# LR1302_LoRaWAN_Gateway_Module_V1_0_915US.net
KiCad netlist of a schematic drawn in EAGLE
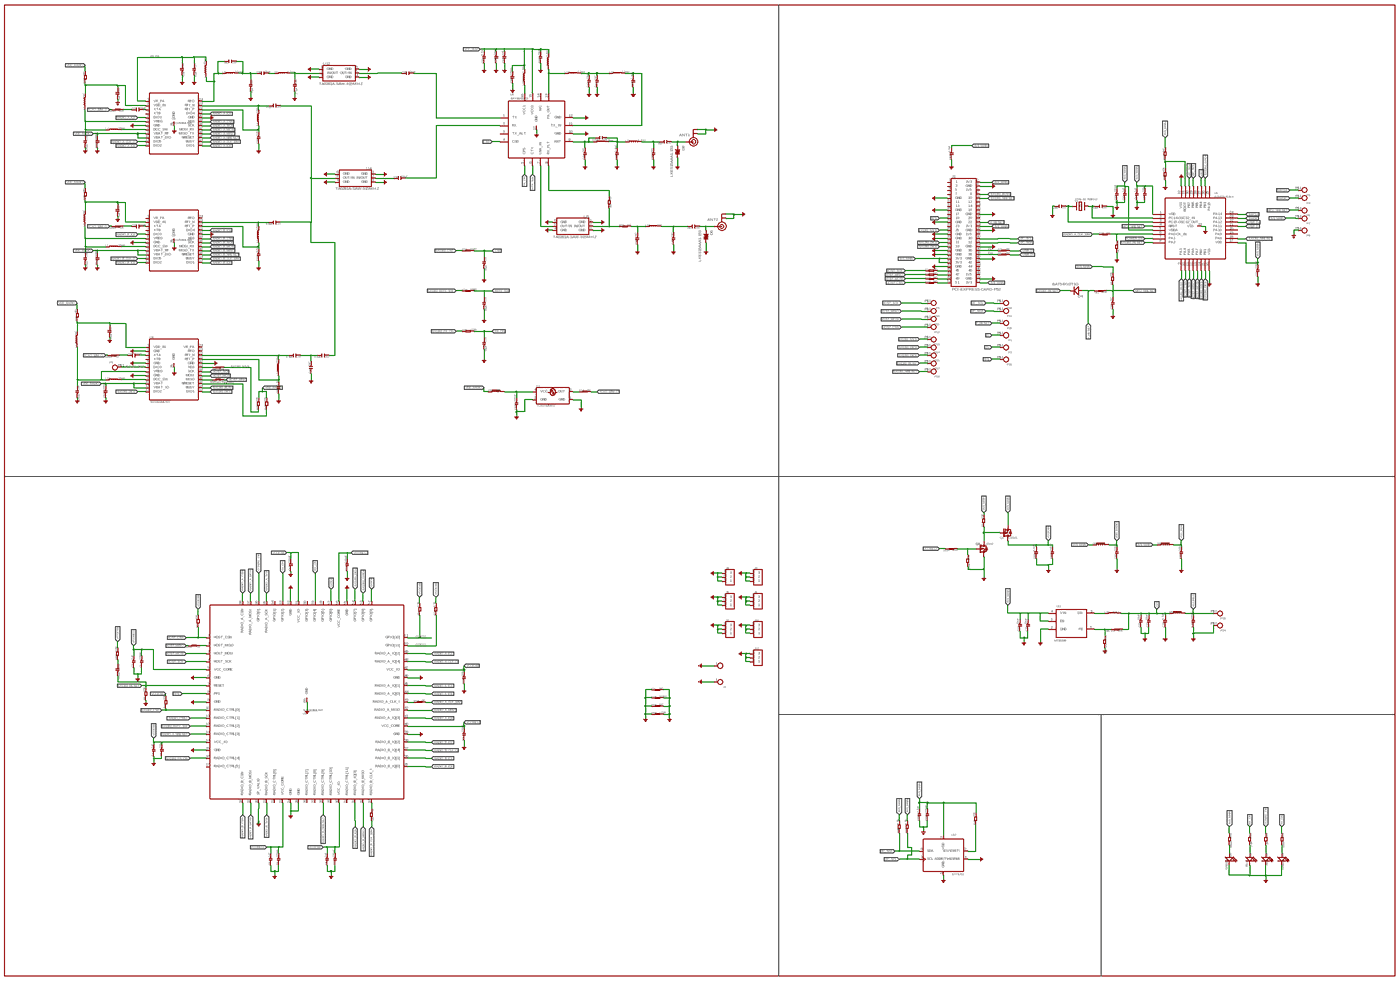
[diagram p0: schematic, sheet 1, overview]
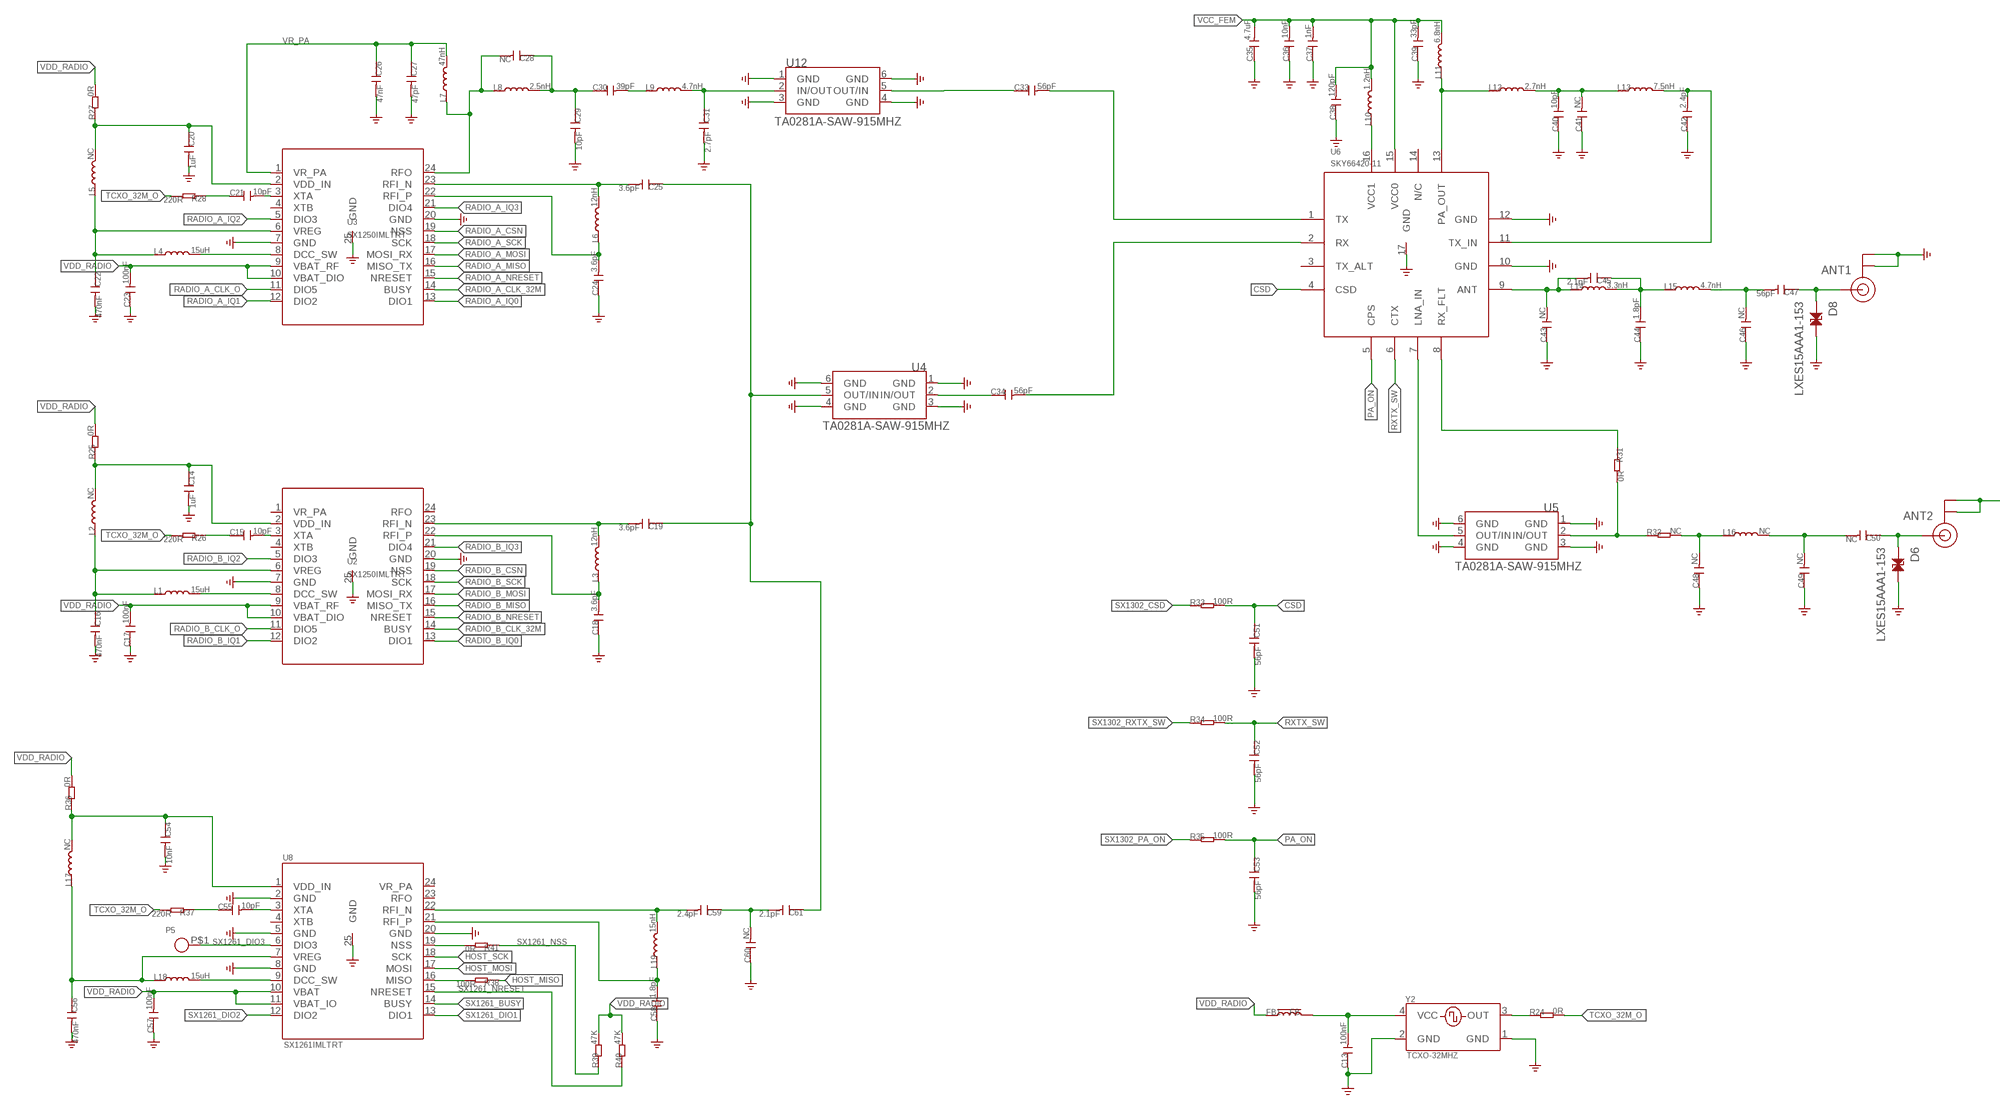
[diagram p1: schematic, sheet 1, part 1 of 4]
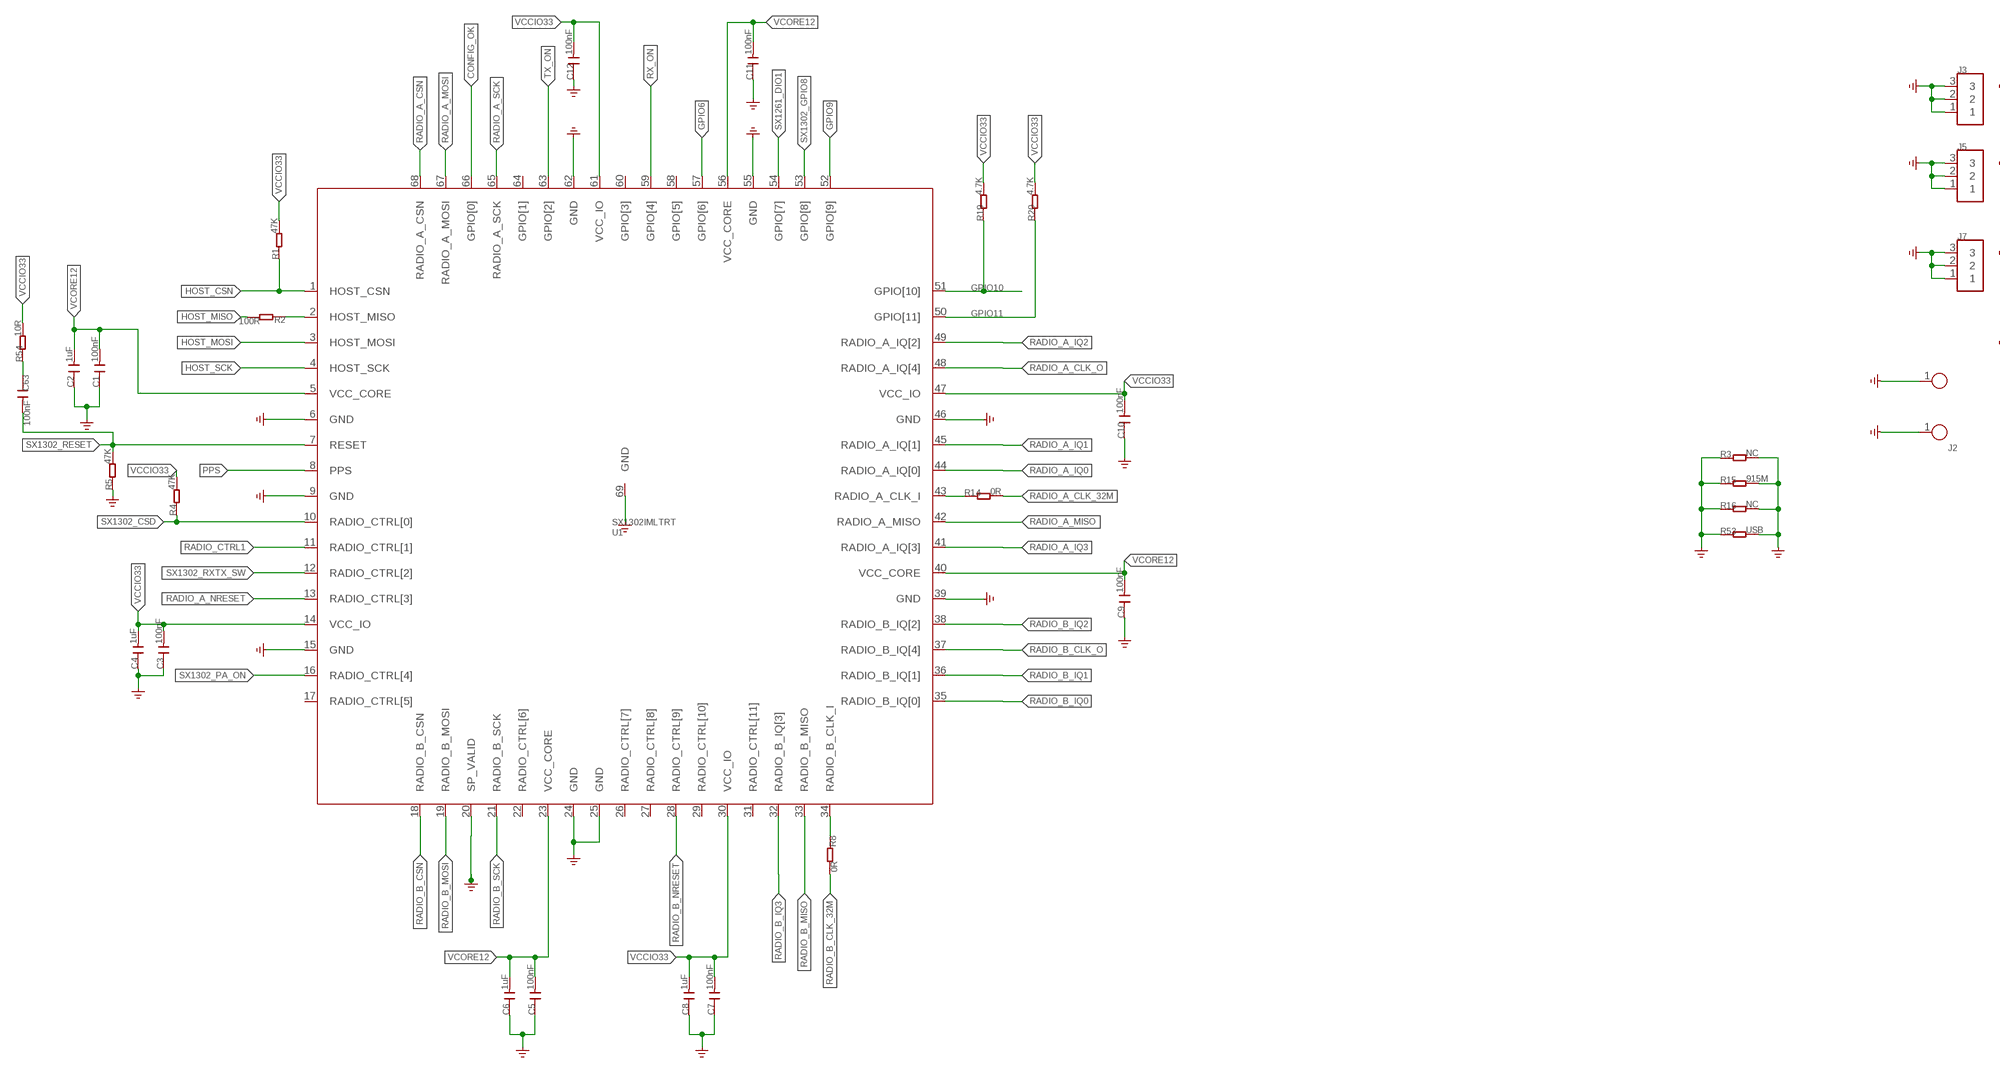
[diagram p2: schematic, sheet 1, part 2 of 4]
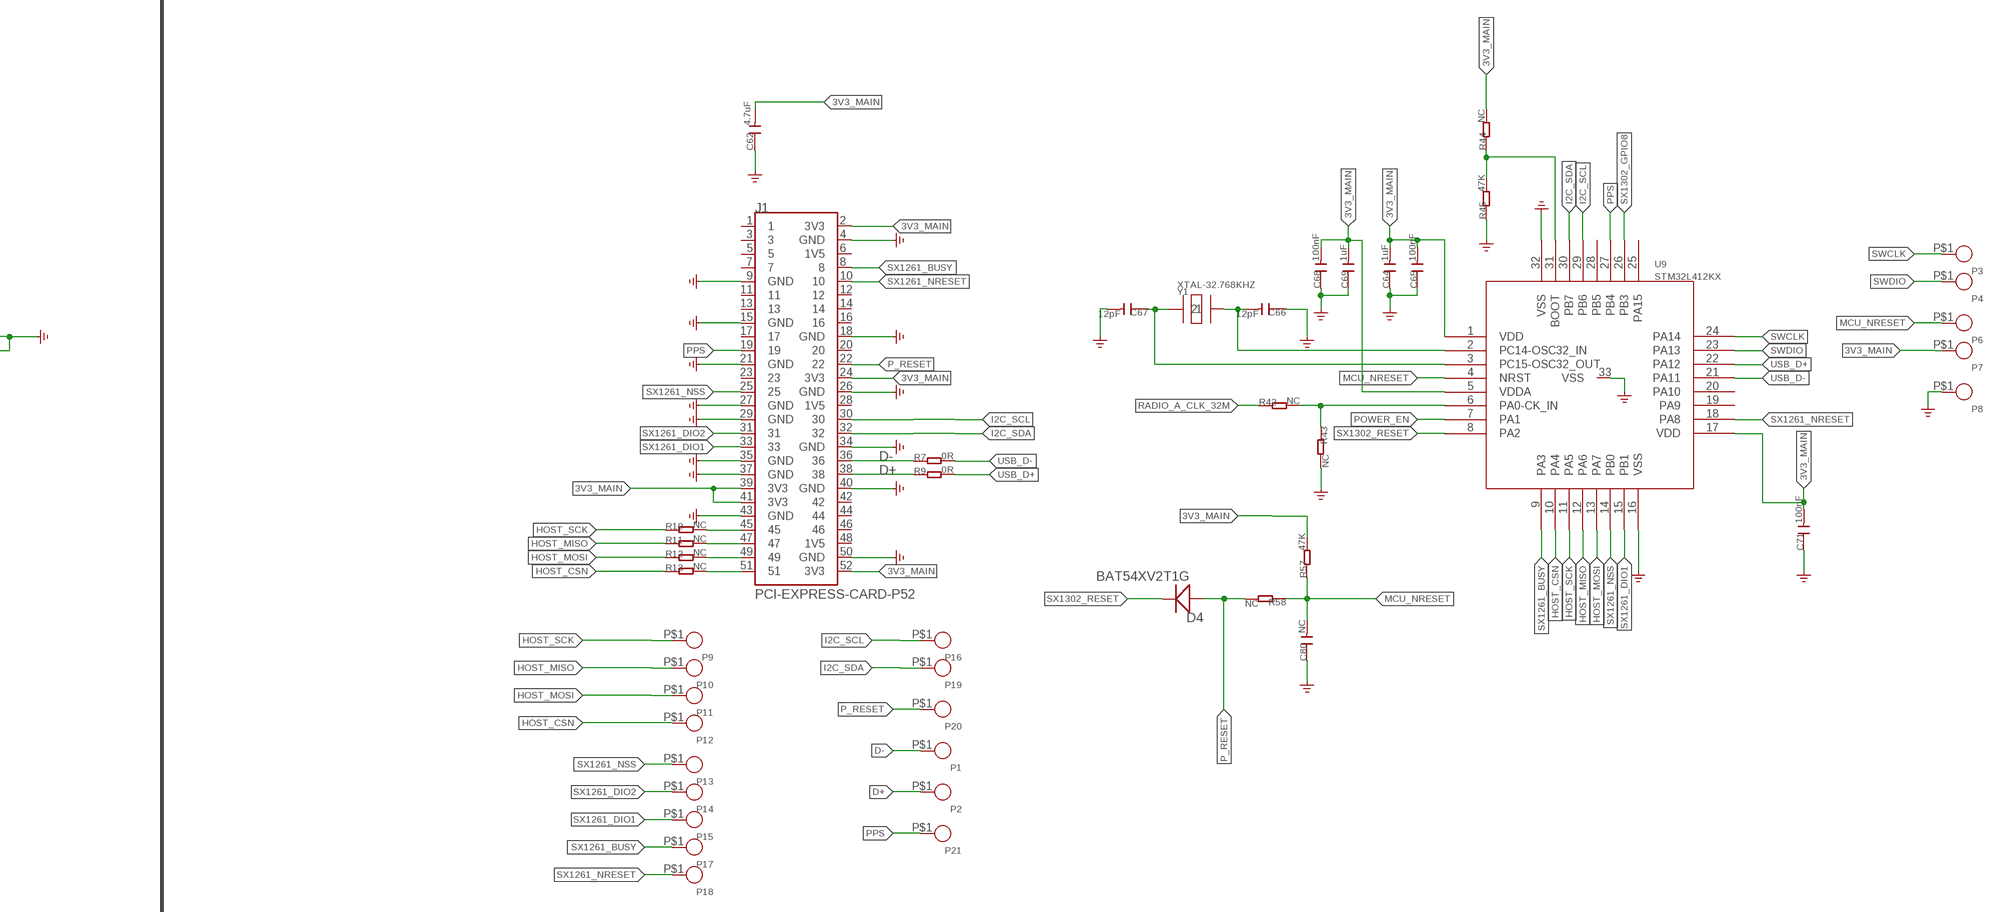
[diagram p3: schematic, sheet 1, part 3 of 4]
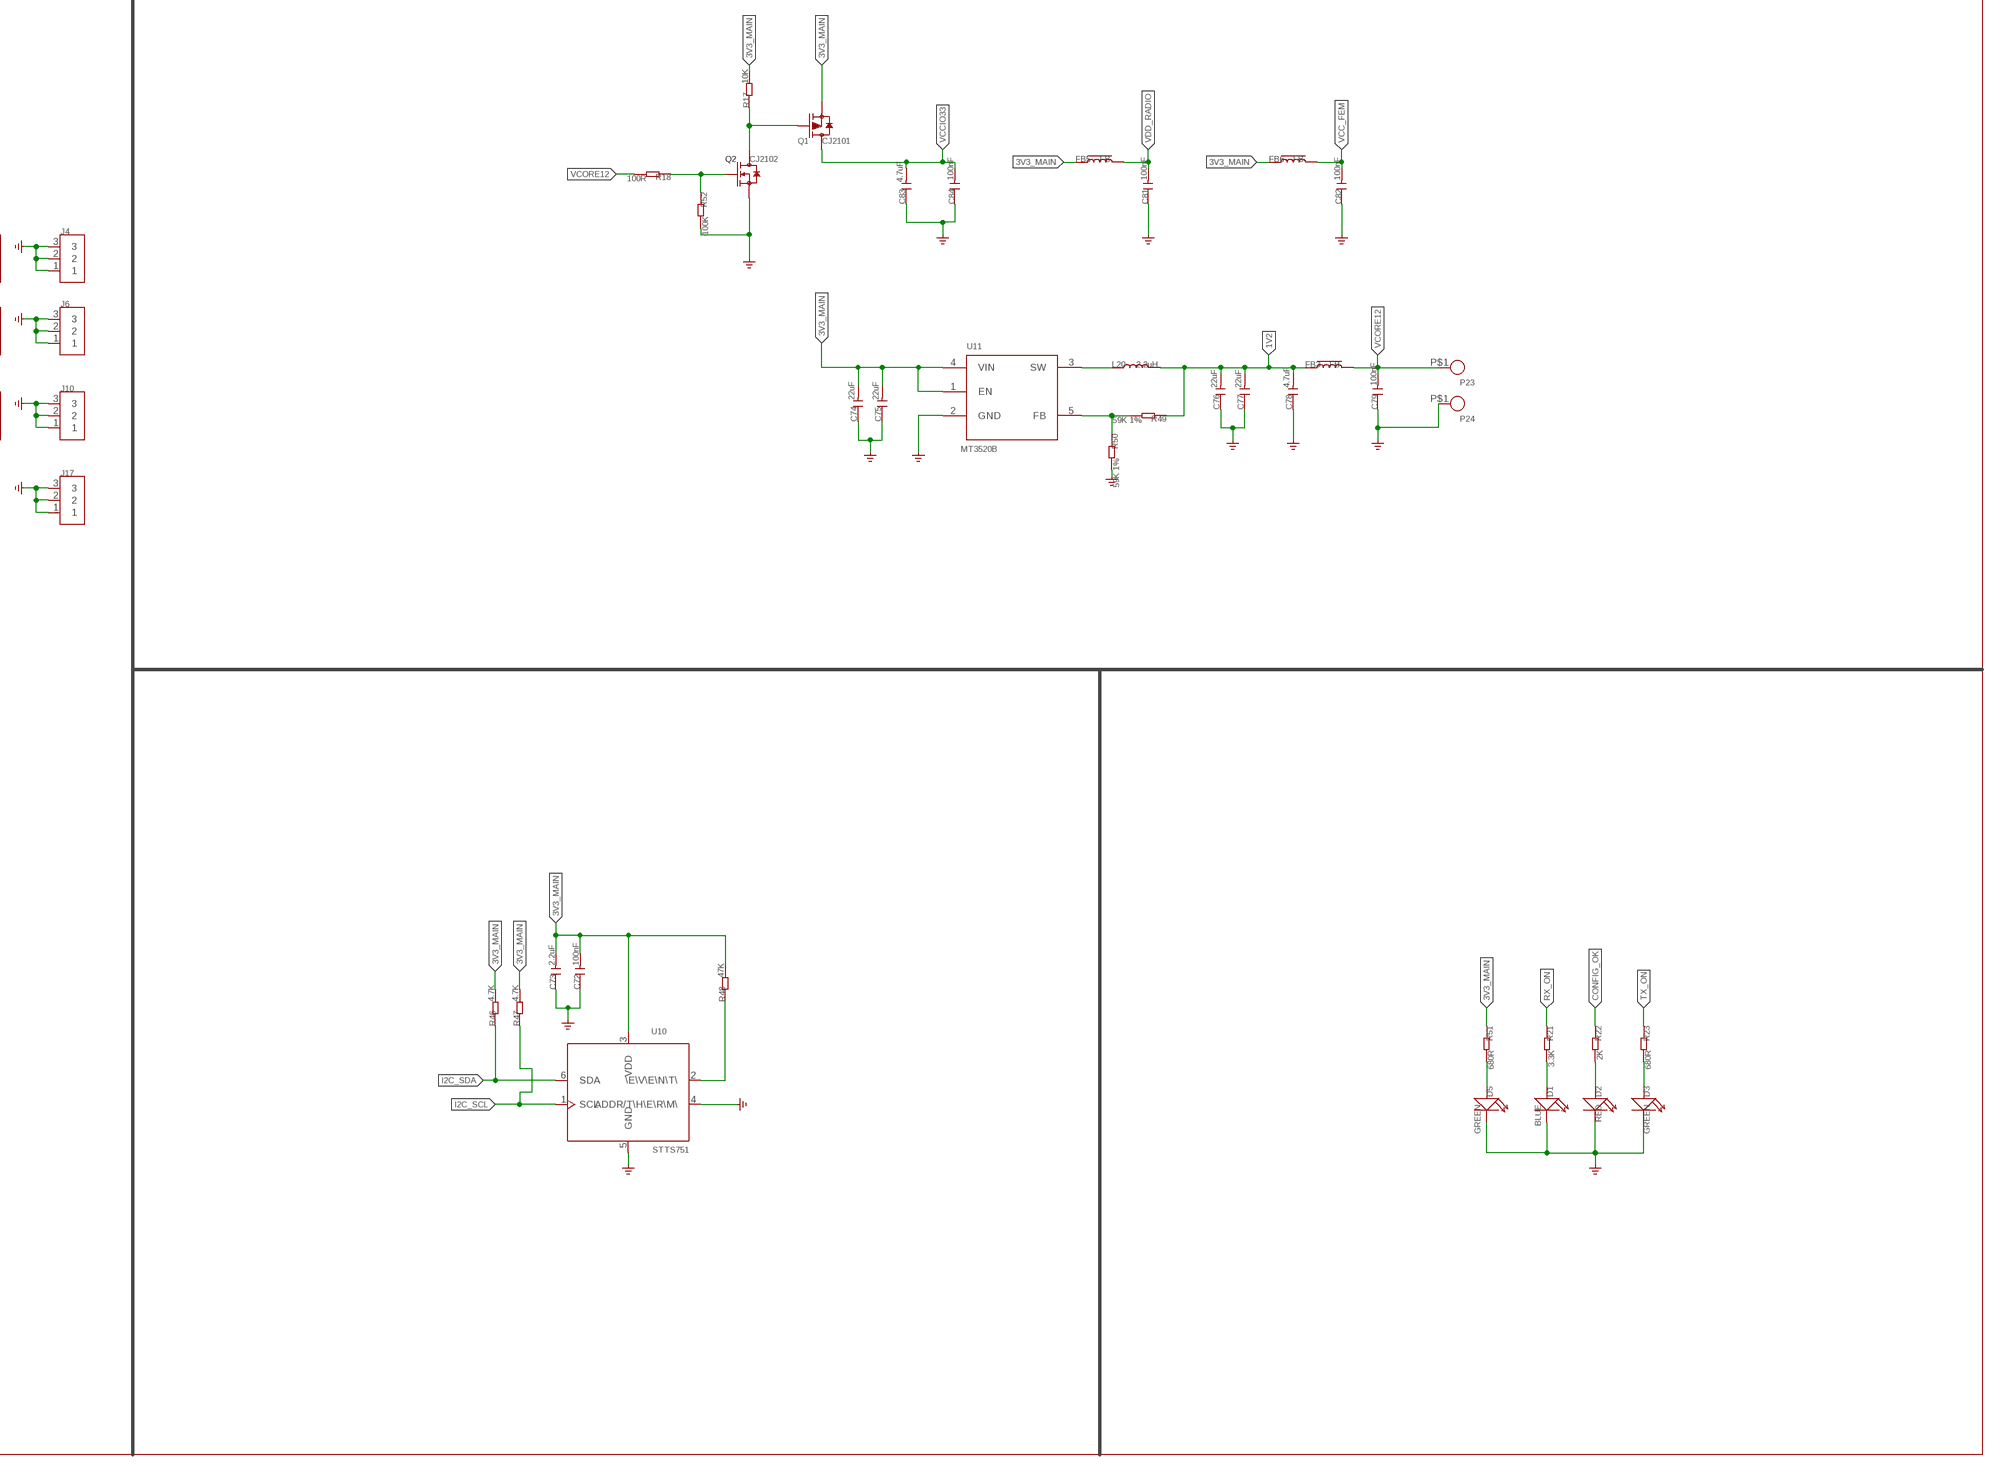
[diagram p4: schematic, sheet 1, part 4 of 4]

(export (version "E")
  (design (tool "Eeschema 10.0.6"))
  (components
    (comp (ref "ANT1")
      (value "U.FL_SMTU.FL-R-SMD")
      (footprint "eagle-import:U.FL-R-SMD")
      (libsource (lib "eagle-import") (part "U.FL_SMTU.FL-R-SMD"))
    )
    (comp (ref "ANT2")
      (value "NC")
      (footprint "eagle-import:U.FL-R-SMD")
      (libsource (lib "eagle-import") (part "U.FL_SMTU.FL-R-SMD"))
    )
    (comp (ref "C1")
      (value "100nF")
      (footprint "eagle-import:C0402")
      (libsource (lib "eagle-import") (part "CAPC0402-1"))
    )
    (comp (ref "C2")
      (value "1uF")
      (footprint "eagle-import:C0402")
      (libsource (lib "eagle-import") (part "CAPC0402-1"))
    )
    (comp (ref "C3")
      (value "100nF")
      (footprint "eagle-import:C0402")
      (libsource (lib "eagle-import") (part "CAPC0402-1"))
    )
    (comp (ref "C4")
      (value "1uF")
      (footprint "eagle-import:C0402")
      (libsource (lib "eagle-import") (part "CAPC0402-1"))
    )
    (comp (ref "C5")
      (value "100nF")
      (footprint "eagle-import:C0402")
      (libsource (lib "eagle-import") (part "CAPC0402-1"))
    )
    (comp (ref "C6")
      (value "1uF")
      (footprint "eagle-import:C0402")
      (libsource (lib "eagle-import") (part "CAPC0402-1"))
    )
    (comp (ref "C7")
      (value "100nF")
      (footprint "eagle-import:C0402")
      (libsource (lib "eagle-import") (part "CAPC0402-1"))
    )
    (comp (ref "C8")
      (value "1uF")
      (footprint "eagle-import:C0402")
      (libsource (lib "eagle-import") (part "CAPC0402-1"))
    )
    (comp (ref "C9")
      (value "100nF")
      (footprint "eagle-import:C0402")
      (libsource (lib "eagle-import") (part "CAPC0402-1"))
    )
    (comp (ref "C10")
      (value "100nF")
      (footprint "eagle-import:C0402")
      (libsource (lib "eagle-import") (part "CAPC0402-1"))
    )
    (comp (ref "C11")
      (value "100nF")
      (footprint "eagle-import:C0402")
      (libsource (lib "eagle-import") (part "CAPC0402-1"))
    )
    (comp (ref "C12")
      (value "100nF")
      (footprint "eagle-import:C0402")
      (libsource (lib "eagle-import") (part "CAPC0402-1"))
    )
    (comp (ref "C13")
      (value "100nF")
      (footprint "eagle-import:C0402")
      (libsource (lib "eagle-import") (part "CAPC0402-1"))
    )
    (comp (ref "C14")
      (value "1uF")
      (footprint "eagle-import:C0402")
      (libsource (lib "eagle-import") (part "CAPC0402-1"))
    )
    (comp (ref "C15")
      (value "10pF")
      (footprint "eagle-import:C0402")
      (libsource (lib "eagle-import") (part "CAPC0402-1"))
    )
    (comp (ref "C16")
      (value "470nF")
      (footprint "eagle-import:C0402")
      (libsource (lib "eagle-import") (part "CAPC0402-1"))
    )
    (comp (ref "C17")
      (value "100nF")
      (footprint "eagle-import:C0402")
      (libsource (lib "eagle-import") (part "CAPC0402-1"))
    )
    (comp (ref "C18")
      (value "3.6pF")
      (footprint "eagle-import:C0402")
      (libsource (lib "eagle-import") (part "CAPC0402-1"))
    )
    (comp (ref "C19")
      (value "3.6pF")
      (footprint "eagle-import:C0402")
      (libsource (lib "eagle-import") (part "CAPC0402-1"))
    )
    (comp (ref "C20")
      (value "1uF")
      (footprint "eagle-import:C0402")
      (libsource (lib "eagle-import") (part "CAPC0402-1"))
    )
    (comp (ref "C21")
      (value "10pF")
      (footprint "eagle-import:C0402")
      (libsource (lib "eagle-import") (part "CAPC0402-1"))
    )
    (comp (ref "C22")
      (value "470nF")
      (footprint "eagle-import:C0402")
      (libsource (lib "eagle-import") (part "CAPC0402-1"))
    )
    (comp (ref "C23")
      (value "100nF")
      (footprint "eagle-import:C0402")
      (libsource (lib "eagle-import") (part "CAPC0402-1"))
    )
    (comp (ref "C24")
      (value "3.6pF")
      (footprint "eagle-import:C0402")
      (libsource (lib "eagle-import") (part "CAPC0402-1"))
    )
    (comp (ref "C25")
      (value "3.6pF")
      (footprint "eagle-import:C0402")
      (libsource (lib "eagle-import") (part "CAPC0402-1"))
    )
    (comp (ref "C26")
      (value "47nF")
      (footprint "eagle-import:C0402")
      (libsource (lib "eagle-import") (part "CAPC0402-1"))
    )
    (comp (ref "C27")
      (value "47pF")
      (footprint "eagle-import:C0402")
      (libsource (lib "eagle-import") (part "CAPC0402-1"))
    )
    (comp (ref "C28")
      (value "NC")
      (footprint "eagle-import:C0402")
      (libsource (lib "eagle-import") (part "CAPC0402-1"))
    )
    (comp (ref "C29")
      (value "10pF")
      (footprint "eagle-import:C0402")
      (libsource (lib "eagle-import") (part "CAPC0402-1"))
    )
    (comp (ref "C30")
      (value "39pF")
      (footprint "eagle-import:C0402")
      (libsource (lib "eagle-import") (part "CAPC0402-1"))
    )
    (comp (ref "C31")
      (value "2.7pF")
      (footprint "eagle-import:C0402")
      (libsource (lib "eagle-import") (part "CAPC0402-1"))
    )
    (comp (ref "C33")
      (value "56pF")
      (footprint "eagle-import:C0402")
      (libsource (lib "eagle-import") (part "CAPC0402-1"))
    )
    (comp (ref "C34")
      (value "56pF")
      (footprint "eagle-import:C0402")
      (libsource (lib "eagle-import") (part "CAPC0402-1"))
    )
    (comp (ref "C35")
      (value "4.7uF")
      (footprint "eagle-import:C0603")
      (libsource (lib "eagle-import") (part "CAP"))
    )
    (comp (ref "C36")
      (value "10nF")
      (footprint "eagle-import:C0402")
      (libsource (lib "eagle-import") (part "CAPC0402-1"))
    )
    (comp (ref "C37")
      (value "1nF")
      (footprint "eagle-import:C0402")
      (libsource (lib "eagle-import") (part "CAPC0402-1"))
    )
    (comp (ref "C38")
      (value "120pF")
      (footprint "eagle-import:C0402")
      (libsource (lib "eagle-import") (part "CAPC0402-1"))
    )
    (comp (ref "C39")
      (value "33pF")
      (footprint "eagle-import:C0402")
      (libsource (lib "eagle-import") (part "CAPC0402-1"))
    )
    (comp (ref "C40")
      (value "10pF")
      (footprint "eagle-import:C0402")
      (libsource (lib "eagle-import") (part "CAPC0402-1"))
    )
    (comp (ref "C41")
      (value "NC")
      (footprint "eagle-import:C0402")
      (libsource (lib "eagle-import") (part "CAPC0402-1"))
    )
    (comp (ref "C42")
      (value "2.4pF")
      (footprint "eagle-import:C0402")
      (libsource (lib "eagle-import") (part "CAPC0402-1"))
    )
    (comp (ref "C43")
      (value "NC")
      (footprint "eagle-import:C0402")
      (libsource (lib "eagle-import") (part "CAPC0402-1"))
    )
    (comp (ref "C44")
      (value "1.8pF")
      (footprint "eagle-import:C0402")
      (libsource (lib "eagle-import") (part "CAPC0402-1"))
    )
    (comp (ref "C45")
      (value "2.1pF")
      (footprint "eagle-import:C0402")
      (libsource (lib "eagle-import") (part "CAPC0402-1"))
    )
    (comp (ref "C46")
      (value "NC")
      (footprint "eagle-import:C0402")
      (libsource (lib "eagle-import") (part "CAPC0402-1"))
    )
    (comp (ref "C47")
      (value "56pF")
      (footprint "eagle-import:C0402")
      (libsource (lib "eagle-import") (part "CAPC0402-1"))
    )
    (comp (ref "C48")
      (value "NC")
      (footprint "eagle-import:C0402")
      (libsource (lib "eagle-import") (part "CAPC0402-1"))
    )
    (comp (ref "C49")
      (value "NC")
      (footprint "eagle-import:C0402")
      (libsource (lib "eagle-import") (part "CAPC0402-1"))
    )
    (comp (ref "C50")
      (value "NC")
      (footprint "eagle-import:C0402")
      (libsource (lib "eagle-import") (part "CAPC0402-1"))
    )
    (comp (ref "C51")
      (value "56pF")
      (footprint "eagle-import:C0402")
      (libsource (lib "eagle-import") (part "CAPC0402-1"))
    )
    (comp (ref "C52")
      (value "56pF")
      (footprint "eagle-import:C0402")
      (libsource (lib "eagle-import") (part "CAPC0402-1"))
    )
    (comp (ref "C53")
      (value "56pF")
      (footprint "eagle-import:C0402")
      (libsource (lib "eagle-import") (part "CAPC0402-1"))
    )
    (comp (ref "C54")
      (value "10nF")
      (footprint "eagle-import:C0402")
      (libsource (lib "eagle-import") (part "CAPC0402-1"))
    )
    (comp (ref "C55")
      (value "10pF")
      (footprint "eagle-import:C0402")
      (libsource (lib "eagle-import") (part "CAPC0402-1"))
    )
    (comp (ref "C56")
      (value "470nF")
      (footprint "eagle-import:C0402")
      (libsource (lib "eagle-import") (part "CAPC0402-1"))
    )
    (comp (ref "C57")
      (value "100nF")
      (footprint "eagle-import:C0402")
      (libsource (lib "eagle-import") (part "CAPC0402-1"))
    )
    (comp (ref "C58")
      (value "1.8pF")
      (footprint "eagle-import:C0402")
      (libsource (lib "eagle-import") (part "CAPC0402-1"))
    )
    (comp (ref "C59")
      (value "2.4pF")
      (footprint "eagle-import:C0402")
      (libsource (lib "eagle-import") (part "CAPC0402-1"))
    )
    (comp (ref "C60")
      (value "NC")
      (footprint "eagle-import:C0402")
      (libsource (lib "eagle-import") (part "CAPC0402-1"))
    )
    (comp (ref "C61")
      (value "2.1pF")
      (footprint "eagle-import:C0402")
      (libsource (lib "eagle-import") (part "CAPC0402-1"))
    )
    (comp (ref "C62")
      (value "4.7uF")
      (footprint "eagle-import:C0603")
      (libsource (lib "eagle-import") (part "CAP"))
    )
    (comp (ref "C63")
      (value "100nF")
      (footprint "eagle-import:C0402")
      (libsource (lib "eagle-import") (part "CAPC0402-1"))
    )
    (comp (ref "C64")
      (value "1uF")
      (footprint "eagle-import:C0402")
      (libsource (lib "eagle-import") (part "CAPC0402-1"))
    )
    (comp (ref "C65")
      (value "100nF")
      (footprint "eagle-import:C0402")
      (libsource (lib "eagle-import") (part "CAPC0402-1"))
    )
    (comp (ref "C66")
      (value "12pF")
      (footprint "eagle-import:C0402")
      (libsource (lib "eagle-import") (part "CAPC0402-1"))
    )
    (comp (ref "C67")
      (value "12pF")
      (footprint "eagle-import:C0402")
      (libsource (lib "eagle-import") (part "CAPC0402-1"))
    )
    (comp (ref "C68")
      (value "100nF")
      (footprint "eagle-import:C0402")
      (libsource (lib "eagle-import") (part "CAPC0402-1"))
    )
    (comp (ref "C69")
      (value "1uF")
      (footprint "eagle-import:C0402")
      (libsource (lib "eagle-import") (part "CAPC0402-1"))
    )
    (comp (ref "C71")
      (value "100nF")
      (footprint "eagle-import:C0402")
      (libsource (lib "eagle-import") (part "CAPC0402-1"))
    )
    (comp (ref "C72")
      (value "100nF")
      (footprint "eagle-import:C0402")
      (libsource (lib "eagle-import") (part "CAPC0402-1"))
    )
    (comp (ref "C73")
      (value "2.2uF")
      (footprint "eagle-import:C0402")
      (libsource (lib "eagle-import") (part "CAPC0402-1"))
    )
    (comp (ref "C74")
      (value "22uF")
      (footprint "eagle-import:C0603")
      (libsource (lib "eagle-import") (part "CAP"))
    )
    (comp (ref "C75")
      (value "22uF")
      (footprint "eagle-import:C0603")
      (libsource (lib "eagle-import") (part "CAP"))
    )
    (comp (ref "C76")
      (value "22uF")
      (footprint "eagle-import:C0603")
      (libsource (lib "eagle-import") (part "CAP"))
    )
    (comp (ref "C77")
      (value "22uF")
      (footprint "eagle-import:C0603")
      (libsource (lib "eagle-import") (part "CAP"))
    )
    (comp (ref "C78")
      (value "4.7uF")
      (footprint "eagle-import:C0603")
      (libsource (lib "eagle-import") (part "CAP"))
    )
    (comp (ref "C79")
      (value "100nF")
      (footprint "eagle-import:C0402")
      (libsource (lib "eagle-import") (part "CAPC0402-1"))
    )
    (comp (ref "C80")
      (value "NC")
      (footprint "eagle-import:C0402")
      (libsource (lib "eagle-import") (part "CAPC0402-1"))
    )
    (comp (ref "C81")
      (value "100nF")
      (footprint "eagle-import:C0402")
      (libsource (lib "eagle-import") (part "CAPC0402-1"))
    )
    (comp (ref "C82")
      (value "100nF")
      (footprint "eagle-import:C0402")
      (libsource (lib "eagle-import") (part "CAPC0402-1"))
    )
    (comp (ref "C83")
      (value "4.7uF")
      (footprint "eagle-import:C0603")
      (libsource (lib "eagle-import") (part "CAP"))
    )
    (comp (ref "C84")
      (value "100nF")
      (footprint "eagle-import:C0402")
      (libsource (lib "eagle-import") (part "CAPC0402-1"))
    )
    (comp (ref "D1")
      (value "BLUE")
      (footprint "eagle-import:LED-0402")
      (libsource (lib "eagle-import") (part "LED-SMT"))
    )
    (comp (ref "D2")
      (value "RED")
      (footprint "eagle-import:LED-0402")
      (libsource (lib "eagle-import") (part "LED-SMT"))
    )
    (comp (ref "D3")
      (value "GREEN")
      (footprint "eagle-import:LED-0402")
      (libsource (lib "eagle-import") (part "LED-SMT"))
    )
    (comp (ref "D4")
      (value "BAT54XV2T1G")
      (footprint "eagle-import:D_SOD523")
      (libsource (lib "eagle-import") (part "DIODE0603"))
    )
    (comp (ref "D5")
      (value "GREEN")
      (footprint "eagle-import:LED-0402")
      (libsource (lib "eagle-import") (part "LED-SMT"))
    )
    (comp (ref "D6")
      (value "LXES15AAA1-153")
      (footprint "eagle-import:D0402")
      (libsource (lib "eagle-import") (part "PESD0402"))
    )
    (comp (ref "D8")
      (value "LXES15AAA1-153")
      (footprint "eagle-import:D0402")
      (libsource (lib "eagle-import") (part "PESD0402"))
    )
    (comp (ref "FB1")
      (value "FB")
      (footprint "eagle-import:L0402")
      (libsource (lib "eagle-import") (part "FB"))
    )
    (comp (ref "FB3")
      (value "FB")
      (footprint "eagle-import:L0402")
      (libsource (lib "eagle-import") (part "FB"))
    )
    (comp (ref "FB5")
      (value "FB")
      (footprint "eagle-import:L0402")
      (libsource (lib "eagle-import") (part "FB"))
    )
    (comp (ref "FB6")
      (value "FB")
      (footprint "eagle-import:L0402")
      (libsource (lib "eagle-import") (part "FB"))
    )
    (comp (ref "J1")
      (value "PCI-EXPRESS-CARD-P52")
      (footprint "eagle-import:PCIE-MINI-S52")
      (libsource (lib "eagle-import") (part "PCI-EXPRESS-CARD-P52"))
    )
    (comp (ref "J2")
      (value "PAD-THO-2.65MM")
      (footprint "eagle-import:PAD-THO-2.6_5MM")
      (libsource (lib "eagle-import") (part "PAD-THO-2.65MM"))
    )
    (comp (ref "J3")
      (value "PBJ-ICSRC6508-SMD")
      (footprint "eagle-import:PBJ-ICSRC6508-SMD")
      (libsource (lib "eagle-import") (part "PBJ-ICSRC6508-SMD"))
    )
    (comp (ref "J4")
      (value "PBJ-ICSRC6508-SMD")
      (footprint "eagle-import:PBJ-ICSRC6508-SMD")
      (libsource (lib "eagle-import") (part "PBJ-ICSRC6508-SMD"))
    )
    (comp (ref "J5")
      (value "PBJ-ICSRC6508-SMD")
      (footprint "eagle-import:PBJ-ICSRC6508-SMD")
      (libsource (lib "eagle-import") (part "PBJ-ICSRC6508-SMD"))
    )
    (comp (ref "J6")
      (value "PBJ-ICSRC6508-SMD")
      (footprint "eagle-import:PBJ-ICSRC6508-SMD")
      (libsource (lib "eagle-import") (part "PBJ-ICSRC6508-SMD"))
    )
    (comp (ref "J7")
      (value "PBJ-ICSRC6508-SMD")
      (footprint "eagle-import:PBJ-ICSRC6508-SMD")
      (libsource (lib "eagle-import") (part "PBJ-ICSRC6508-SMD"))
    )
    (comp (ref "J10")
      (value "PBJ-ICSRC6508-SMD")
      (footprint "eagle-import:PBJ-ICSRC6508-SMD")
      (libsource (lib "eagle-import") (part "PBJ-ICSRC6508-SMD"))
    )
    (comp (ref "J11")
      (value "PAD-THO-2.65MM")
      (footprint "eagle-import:PAD-THO-2.6_5MM")
      (libsource (lib "eagle-import") (part "PAD-THO-2.65MM"))
    )
    (comp (ref "J17")
      (value "PBJ-ICSRC6508-SMD")
      (footprint "eagle-import:PBJ-ICSRC6508-SMD")
      (libsource (lib "eagle-import") (part "PBJ-ICSRC6508-SMD"))
    )
    (comp (ref "L1")
      (value "15uH")
      (footprint "eagle-import:L0805")
      (libsource (lib "eagle-import") (part "L0805"))
    )
    (comp (ref "L2")
      (value "NC")
      (footprint "eagle-import:L0402")
      (libsource (lib "eagle-import") (part "L0402"))
    )
    (comp (ref "L3")
      (value "12nH")
      (footprint "eagle-import:L0402")
      (libsource (lib "eagle-import") (part "L0402"))
    )
    (comp (ref "L4")
      (value "15uH")
      (footprint "eagle-import:L0805")
      (libsource (lib "eagle-import") (part "L0805"))
    )
    (comp (ref "L5")
      (value "NC")
      (footprint "eagle-import:L0402")
      (libsource (lib "eagle-import") (part "L0402"))
    )
    (comp (ref "L6")
      (value "12nH")
      (footprint "eagle-import:L0402")
      (libsource (lib "eagle-import") (part "L0402"))
    )
    (comp (ref "L7")
      (value "47nH")
      (footprint "eagle-import:L0402")
      (libsource (lib "eagle-import") (part "L0402"))
    )
    (comp (ref "L8")
      (value "2.5nH")
      (footprint "eagle-import:L0402")
      (libsource (lib "eagle-import") (part "L0402"))
    )
    (comp (ref "L9")
      (value "4.7nH")
      (footprint "eagle-import:L0402")
      (libsource (lib "eagle-import") (part "L0402"))
    )
    (comp (ref "L10")
      (value "1.2nH")
      (footprint "eagle-import:L0402")
      (libsource (lib "eagle-import") (part "L0402"))
    )
    (comp (ref "L11")
      (value "6.8nH")
      (footprint "eagle-import:L0402")
      (libsource (lib "eagle-import") (part "L0402"))
    )
    (comp (ref "L12")
      (value "2.7nH")
      (footprint "eagle-import:L0402")
      (libsource (lib "eagle-import") (part "L0402"))
    )
    (comp (ref "L13")
      (value "7.5nH")
      (footprint "eagle-import:L0402")
      (libsource (lib "eagle-import") (part "L0402"))
    )
    (comp (ref "L14")
      (value "3.3nH")
      (footprint "eagle-import:L0402")
      (libsource (lib "eagle-import") (part "L0402"))
    )
    (comp (ref "L15")
      (value "4.7nH")
      (footprint "eagle-import:L0402")
      (libsource (lib "eagle-import") (part "L0402"))
    )
    (comp (ref "L16")
      (value "NC")
      (footprint "eagle-import:L0402")
      (libsource (lib "eagle-import") (part "L0402"))
    )
    (comp (ref "L17")
      (value "NC")
      (footprint "eagle-import:L0402")
      (libsource (lib "eagle-import") (part "L0402"))
    )
    (comp (ref "L18")
      (value "15uH")
      (footprint "eagle-import:L0805")
      (libsource (lib "eagle-import") (part "L0805"))
    )
    (comp (ref "L19")
      (value "15nH")
      (footprint "eagle-import:L0402")
      (libsource (lib "eagle-import") (part "L0402"))
    )
    (comp (ref "L20")
      (value "2.2uH")
      (footprint "eagle-import:L3015_SMD")
      (libsource (lib "eagle-import") (part "L"))
    )
    (comp (ref "P1")
      (value "TEST_PADPAD-1.0MM")
      (footprint "eagle-import:TEST_PAD-1.0MM")
      (libsource (lib "eagle-import") (part "TEST_PADPAD-1.0MM"))
    )
    (comp (ref "P2")
      (value "TEST_PADPAD-1.0MM")
      (footprint "eagle-import:TEST_PAD-1.0MM")
      (libsource (lib "eagle-import") (part "TEST_PADPAD-1.0MM"))
    )
    (comp (ref "P3")
      (value "TEST_PADPAD-1.0MM")
      (footprint "eagle-import:TEST_PAD-1.0MM")
      (libsource (lib "eagle-import") (part "TEST_PADPAD-1.0MM"))
    )
    (comp (ref "P4")
      (value "TEST_PADPAD-1.0MM")
      (footprint "eagle-import:TEST_PAD-1.0MM")
      (libsource (lib "eagle-import") (part "TEST_PADPAD-1.0MM"))
    )
    (comp (ref "P5")
      (value "TEST_PADPAD-1.0MM")
      (footprint "eagle-import:TEST_PAD-1.0MM")
      (libsource (lib "eagle-import") (part "TEST_PADPAD-1.0MM"))
    )
    (comp (ref "P6")
      (value "TEST_PADPAD-1.0MM")
      (footprint "eagle-import:TEST_PAD-1.0MM")
      (libsource (lib "eagle-import") (part "TEST_PADPAD-1.0MM"))
    )
    (comp (ref "P7")
      (value "TEST_PADPAD-1.0MM")
      (footprint "eagle-import:TEST_PAD-1.0MM")
      (libsource (lib "eagle-import") (part "TEST_PADPAD-1.0MM"))
    )
    (comp (ref "P8")
      (value "TEST_PADPAD-1.0MM")
      (footprint "eagle-import:TEST_PAD-1.0MM")
      (libsource (lib "eagle-import") (part "TEST_PADPAD-1.0MM"))
    )
    (comp (ref "P9")
      (value "TEST_PADPAD-1.0MM")
      (footprint "eagle-import:TEST_PAD-1.0MM")
      (libsource (lib "eagle-import") (part "TEST_PADPAD-1.0MM"))
    )
    (comp (ref "P10")
      (value "TEST_PADPAD-1.0MM")
      (footprint "eagle-import:TEST_PAD-1.0MM")
      (libsource (lib "eagle-import") (part "TEST_PADPAD-1.0MM"))
    )
    (comp (ref "P11")
      (value "TEST_PADPAD-1.0MM")
      (footprint "eagle-import:TEST_PAD-1.0MM")
      (libsource (lib "eagle-import") (part "TEST_PADPAD-1.0MM"))
    )
    (comp (ref "P12")
      (value "TEST_PADPAD-1.0MM")
      (footprint "eagle-import:TEST_PAD-1.0MM")
      (libsource (lib "eagle-import") (part "TEST_PADPAD-1.0MM"))
    )
    (comp (ref "P13")
      (value "TEST_PADPAD-1.0MM")
      (footprint "eagle-import:TEST_PAD-1.0MM")
      (libsource (lib "eagle-import") (part "TEST_PADPAD-1.0MM"))
    )
    (comp (ref "P14")
      (value "TEST_PADPAD-1.0MM")
      (footprint "eagle-import:TEST_PAD-1.0MM")
      (libsource (lib "eagle-import") (part "TEST_PADPAD-1.0MM"))
    )
    (comp (ref "P15")
      (value "TEST_PADPAD-1.0MM")
      (footprint "eagle-import:TEST_PAD-1.0MM")
      (libsource (lib "eagle-import") (part "TEST_PADPAD-1.0MM"))
    )
    (comp (ref "P16")
      (value "TEST_PADPAD-1.0MM")
      (footprint "eagle-import:TEST_PAD-1.0MM")
      (libsource (lib "eagle-import") (part "TEST_PADPAD-1.0MM"))
    )
    (comp (ref "P17")
      (value "TEST_PADPAD-1.0MM")
      (footprint "eagle-import:TEST_PAD-1.0MM")
      (libsource (lib "eagle-import") (part "TEST_PADPAD-1.0MM"))
    )
    (comp (ref "P18")
      (value "TEST_PADPAD-1.0MM")
      (footprint "eagle-import:TEST_PAD-1.0MM")
      (libsource (lib "eagle-import") (part "TEST_PADPAD-1.0MM"))
    )
    (comp (ref "P19")
      (value "TEST_PADPAD-1.0MM")
      (footprint "eagle-import:TEST_PAD-1.0MM")
      (libsource (lib "eagle-import") (part "TEST_PADPAD-1.0MM"))
    )
    (comp (ref "P20")
      (value "TEST_PADPAD-1.0MM")
      (footprint "eagle-import:TEST_PAD-1.0MM")
      (libsource (lib "eagle-import") (part "TEST_PADPAD-1.0MM"))
    )
    (comp (ref "P21")
      (value "TEST_PADPAD-1.0MM")
      (footprint "eagle-import:TEST_PAD-1.0MM")
      (libsource (lib "eagle-import") (part "TEST_PADPAD-1.0MM"))
    )
    (comp (ref "P23")
      (value "TEST_PADPAD-1.0MM")
      (footprint "eagle-import:TEST_PAD-1.0MM")
      (libsource (lib "eagle-import") (part "TEST_PADPAD-1.0MM"))
    )
    (comp (ref "P24")
      (value "TEST_PADPAD-1.0MM")
      (footprint "eagle-import:TEST_PAD-1.0MM")
      (libsource (lib "eagle-import") (part "TEST_PADPAD-1.0MM"))
    )
    (comp (ref "Q1")
      (value "CJ2101")
      (footprint "eagle-import:MOS_SOT323")
      (libsource (lib "eagle-import") (part "MOSFET-P"))
    )
    (comp (ref "Q2")
      (value "CJ2102")
      (footprint "eagle-import:MOS_SOT323")
      (libsource (lib "eagle-import") (part "MOSFET-NSI1304BDL"))
    )
    (comp (ref "R1")
      (value "47K")
      (footprint "eagle-import:R0402")
      (libsource (lib "eagle-import") (part "RES-0402"))
    )
    (comp (ref "R2")
      (value "100R")
      (footprint "eagle-import:R0402")
      (libsource (lib "eagle-import") (part "RES-0402"))
    )
    (comp (ref "R3")
      (value "NC")
      (footprint "eagle-import:R0402")
      (libsource (lib "eagle-import") (part "RES-0402"))
    )
    (comp (ref "R4")
      (value "47K")
      (footprint "eagle-import:R0402")
      (libsource (lib "eagle-import") (part "RES-0402"))
    )
    (comp (ref "R5")
      (value "47K")
      (footprint "eagle-import:R0402")
      (libsource (lib "eagle-import") (part "RES-0402"))
    )
    (comp (ref "R7")
      (value "0R")
      (footprint "eagle-import:R0402")
      (libsource (lib "eagle-import") (part "RES-0402"))
    )
    (comp (ref "R8")
      (value "0R")
      (footprint "eagle-import:R0402")
      (libsource (lib "eagle-import") (part "RES-0402"))
    )
    (comp (ref "R9")
      (value "0R")
      (footprint "eagle-import:R0402")
      (libsource (lib "eagle-import") (part "RES-0402"))
    )
    (comp (ref "R10")
      (value "NC")
      (footprint "eagle-import:R0402")
      (libsource (lib "eagle-import") (part "RES-0402"))
    )
    (comp (ref "R11")
      (value "NC")
      (footprint "eagle-import:R0402")
      (libsource (lib "eagle-import") (part "RES-0402"))
    )
    (comp (ref "R12")
      (value "NC")
      (footprint "eagle-import:R0402")
      (libsource (lib "eagle-import") (part "RES-0402"))
    )
    (comp (ref "R13")
      (value "NC")
      (footprint "eagle-import:R0402")
      (libsource (lib "eagle-import") (part "RES-0402"))
    )
    (comp (ref "R14")
      (value "0R")
      (footprint "eagle-import:R0402")
      (libsource (lib "eagle-import") (part "RES-0402"))
    )
    (comp (ref "R15")
      (value "915M")
      (footprint "eagle-import:R0402")
      (libsource (lib "eagle-import") (part "RES-0402"))
    )
    (comp (ref "R16")
      (value "NC")
      (footprint "eagle-import:R0402")
      (libsource (lib "eagle-import") (part "RES-0402"))
    )
    (comp (ref "R17")
      (value "10K")
      (footprint "eagle-import:R0402")
      (libsource (lib "eagle-import") (part "RES-0402"))
    )
    (comp (ref "R18")
      (value "100R")
      (footprint "eagle-import:R0402")
      (libsource (lib "eagle-import") (part "RES-0402"))
    )
    (comp (ref "R19")
      (value "4.7K")
      (footprint "eagle-import:R0402")
      (libsource (lib "eagle-import") (part "RES-0402"))
    )
    (comp (ref "R20")
      (value "4.7K")
      (footprint "eagle-import:R0402")
      (libsource (lib "eagle-import") (part "RES-0402"))
    )
    (comp (ref "R21")
      (value "3.3K")
      (footprint "eagle-import:R0402")
      (libsource (lib "eagle-import") (part "RES-0402"))
    )
    (comp (ref "R22")
      (value "2K")
      (footprint "eagle-import:R0402")
      (libsource (lib "eagle-import") (part "RES-0402"))
    )
    (comp (ref "R23")
      (value "680R")
      (footprint "eagle-import:R0402")
      (libsource (lib "eagle-import") (part "RES-0402"))
    )
    (comp (ref "R24")
      (value "0R")
      (footprint "eagle-import:R0402")
      (libsource (lib "eagle-import") (part "RES-0402"))
    )
    (comp (ref "R25")
      (value "0R")
      (footprint "eagle-import:R0402")
      (libsource (lib "eagle-import") (part "RES-0402"))
    )
    (comp (ref "R26")
      (value "220R")
      (footprint "eagle-import:R0402")
      (libsource (lib "eagle-import") (part "RES-0402"))
    )
    (comp (ref "R27")
      (value "0R")
      (footprint "eagle-import:R0402")
      (libsource (lib "eagle-import") (part "RES-0402"))
    )
    (comp (ref "R28")
      (value "220R")
      (footprint "eagle-import:R0402")
      (libsource (lib "eagle-import") (part "RES-0402"))
    )
    (comp (ref "R31")
      (value "0R")
      (footprint "eagle-import:R0402")
      (libsource (lib "eagle-import") (part "RES-0402"))
    )
    (comp (ref "R32")
      (value "NC")
      (footprint "eagle-import:R0402")
      (libsource (lib "eagle-import") (part "RES-0402"))
    )
    (comp (ref "R33")
      (value "100R")
      (footprint "eagle-import:R0402")
      (libsource (lib "eagle-import") (part "RES-0402"))
    )
    (comp (ref "R34")
      (value "100R")
      (footprint "eagle-import:R0402")
      (libsource (lib "eagle-import") (part "RES-0402"))
    )
    (comp (ref "R35")
      (value "100R")
      (footprint "eagle-import:R0402")
      (libsource (lib "eagle-import") (part "RES-0402"))
    )
    (comp (ref "R36")
      (value "0R")
      (footprint "eagle-import:R0402")
      (libsource (lib "eagle-import") (part "RES-0402"))
    )
    (comp (ref "R37")
      (value "220R")
      (footprint "eagle-import:R0402")
      (libsource (lib "eagle-import") (part "RES-0402"))
    )
    (comp (ref "R38")
      (value "100R")
      (footprint "eagle-import:R0402")
      (libsource (lib "eagle-import") (part "RES-0402"))
    )
    (comp (ref "R39")
      (value "47K")
      (footprint "eagle-import:R0402")
      (libsource (lib "eagle-import") (part "RES-0402"))
    )
    (comp (ref "R40")
      (value "47K")
      (footprint "eagle-import:R0402")
      (libsource (lib "eagle-import") (part "RES-0402"))
    )
    (comp (ref "R41")
      (value "0R")
      (footprint "eagle-import:R0402")
      (libsource (lib "eagle-import") (part "RES-0402"))
    )
    (comp (ref "R42")
      (value "NC")
      (footprint "eagle-import:R0402")
      (libsource (lib "eagle-import") (part "RES-0402"))
    )
    (comp (ref "R43")
      (value "NC")
      (footprint "eagle-import:R0402")
      (libsource (lib "eagle-import") (part "RES-0402"))
    )
    (comp (ref "R44")
      (value "NC")
      (footprint "eagle-import:R0402")
      (libsource (lib "eagle-import") (part "RES-0402"))
    )
    (comp (ref "R45")
      (value "47K")
      (footprint "eagle-import:R0402")
      (libsource (lib "eagle-import") (part "RES-0402"))
    )
    (comp (ref "R46")
      (value "4.7K")
      (footprint "eagle-import:R0402")
      (libsource (lib "eagle-import") (part "RES-0402"))
    )
    (comp (ref "R47")
      (value "4.7K")
      (footprint "eagle-import:R0402")
      (libsource (lib "eagle-import") (part "RES-0402"))
    )
    (comp (ref "R48")
      (value "47K")
      (footprint "eagle-import:R0402")
      (libsource (lib "eagle-import") (part "RES-0402"))
    )
    (comp (ref "R49")
      (value "59K 1%")
      (footprint "eagle-import:R0402")
      (libsource (lib "eagle-import") (part "RES-0402"))
    )
    (comp (ref "R50")
      (value "59K 1%")
      (footprint "eagle-import:R0402")
      (libsource (lib "eagle-import") (part "RES-0402"))
    )
    (comp (ref "R51")
      (value "680R")
      (footprint "eagle-import:R0402")
      (libsource (lib "eagle-import") (part "RES-0402"))
    )
    (comp (ref "R52")
      (value "100K")
      (footprint "eagle-import:R0402")
      (libsource (lib "eagle-import") (part "RES-0402"))
    )
    (comp (ref "R53")
      (value "USB")
      (footprint "eagle-import:R0402")
      (libsource (lib "eagle-import") (part "RES-0402"))
    )
    (comp (ref "R54")
      (value "10R")
      (footprint "eagle-import:R0402")
      (libsource (lib "eagle-import") (part "RES-0402"))
    )
    (comp (ref "R57")
      (value "47K")
      (footprint "eagle-import:R0402")
      (libsource (lib "eagle-import") (part "RES-0402"))
    )
    (comp (ref "R58")
      (value "NC")
      (footprint "eagle-import:R0402")
      (libsource (lib "eagle-import") (part "RES-0402"))
    )
    (comp (ref "U1")
      (value "SX1302IMLTRT")
      (footprint "eagle-import:QFN68-7_7MM")
      (libsource (lib "eagle-import") (part "SX1302IMLTRT"))
    )
    (comp (ref "U2")
      (value "SX1250IMLTRT")
      (footprint "eagle-import:QFN24-4_4MM")
      (libsource (lib "eagle-import") (part "SX1250IMLTRT"))
    )
    (comp (ref "U3")
      (value "SX1250IMLTRT")
      (footprint "eagle-import:QFN24-4_4MM")
      (libsource (lib "eagle-import") (part "SX1250IMLTRT"))
    )
    (comp (ref "U4")
      (value "TA0281A-SAW-915MHZ")
      (footprint "eagle-import:SAW-SMD6-3_3MM")
      (libsource (lib "eagle-import") (part "TA0801A-SAW-868MHZ"))
    )
    (comp (ref "U5")
      (value "TA0281A-SAW-915MHZ")
      (footprint "eagle-import:SAW-SMD6-3_3MM")
      (libsource (lib "eagle-import") (part "TA0801A-SAW-868MHZ"))
    )
    (comp (ref "U6")
      (value "SKY66420-11")
      (footprint "eagle-import:MCM-16-EP(3X3)")
      (libsource (lib "eagle-import") (part "SKY66420-11"))
    )
    (comp (ref "U8")
      (value "SX1261IMLTRT")
      (footprint "eagle-import:QFN24-4_4MM")
      (libsource (lib "eagle-import") (part "SX1261IMLTRT"))
    )
    (comp (ref "U9")
      (value "STM32L412KX")
      (footprint "eagle-import:UFQFPN-32-5_5MM")
      (libsource (lib "eagle-import") (part "STM32L412KX"))
    )
    (comp (ref "U10")
      (value "STTS751")
      (footprint "eagle-import:UDFN-6(2X2)")
      (libsource (lib "eagle-import") (part "STTS751"))
    )
    (comp (ref "U11")
      (value "MT3520B")
      (footprint "eagle-import:IC_SOT23-5")
      (libsource (lib "eagle-import") (part "MT3520B"))
    )
    (comp (ref "U12")
      (value "TA0281A-SAW-915MHZ")
      (footprint "eagle-import:SAW-SMD6-3_3MM")
      (libsource (lib "eagle-import") (part "TA0801A-SAW-868MHZ"))
    )
    (comp (ref "Y1")
      (value "XTAL-32.768KHZ")
      (footprint "eagle-import:XATL-3215-SMD")
      (libsource (lib "eagle-import") (part "XTAL-32.768KHZ"))
    )
    (comp (ref "Y2")
      (value "TCXO-32MHZ")
      (footprint "eagle-import:TXCO-SMD2.0_1.6")
      (libsource (lib "eagle-import") (part "TCXO-32MHZ"))
    )
  )
  (nets
    (net (code "1") (name "/GPIO10") (class "Default")
      (node (ref "R19") (pin "1") (pinfunction "1_1") (pintype "passive"))
      (node (ref "U1") (pin "51") (pinfunction "GPIO[10]_51") (pintype "passive"))
    )
    (net (code "2") (name "/GPIO11") (class "Default")
      (node (ref "R20") (pin "1") (pinfunction "1_1") (pintype "passive"))
      (node (ref "U1") (pin "50") (pinfunction "GPIO[11]_50") (pintype "passive"))
    )
    (net (code "3") (name "/SX1261_DIO3") (class "Default")
      (node (ref "P5") (pin "P$1") (pinfunction "P$1_P$1") (pintype "bidirectional"))
      (node (ref "U8") (pin "6") (pinfunction "DIO3_6") (pintype "bidirectional"))
    )
    (net (code "4") (name "/VR_PA") (class "Default")
      (node (ref "C26") (pin "1") (pinfunction "1_1") (pintype "passive"))
      (node (ref "C27") (pin "1") (pinfunction "1_1") (pintype "passive"))
      (node (ref "L7") (pin "2") (pinfunction "2_2") (pintype "passive"))
      (node (ref "U3") (pin "1") (pinfunction "VR_PA_1") (pintype "bidirectional"))
    )
    (net (code "5") (name "1V2") (class "Default")
      (node (ref "C76") (pin "2") (pinfunction "2_2") (pintype "passive"))
      (node (ref "C77") (pin "2") (pinfunction "2_2") (pintype "passive"))
      (node (ref "C78") (pin "2") (pinfunction "2_2") (pintype "passive"))
      (node (ref "FB3") (pin "1") (pinfunction "1_1") (pintype "passive"))
      (node (ref "L20") (pin "2") (pinfunction "2_2") (pintype "passive"))
      (node (ref "R49") (pin "1") (pinfunction "1_1") (pintype "passive"))
    )
    (net (code "6") (name "3V3_MAIN") (class "Default")
      (node (ref "C62") (pin "2") (pinfunction "2_2") (pintype "passive"))
      (node (ref "C64") (pin "2") (pinfunction "2_2") (pintype "passive"))
      (node (ref "C65") (pin "2") (pinfunction "2_2") (pintype "passive"))
      (node (ref "C68") (pin "2") (pinfunction "2_2") (pintype "passive"))
      (node (ref "C69") (pin "2") (pinfunction "2_2") (pintype "passive"))
      (node (ref "C71") (pin "2") (pinfunction "2_2") (pintype "passive"))
      (node (ref "C72") (pin "2") (pinfunction "2_2") (pintype "passive"))
      (node (ref "C73") (pin "2") (pinfunction "2_2") (pintype "passive"))
      (node (ref "C74") (pin "2") (pinfunction "2_2") (pintype "passive"))
      (node (ref "C75") (pin "2") (pinfunction "2_2") (pintype "passive"))
      (node (ref "FB5") (pin "1") (pinfunction "1_1") (pintype "passive"))
      (node (ref "FB6") (pin "1") (pinfunction "1_1") (pintype "passive"))
      (node (ref "J1") (pin "2") (pinfunction "3V3_2") (pintype "bidirectional"))
      (node (ref "J1") (pin "24") (pinfunction "3V3_24") (pintype "bidirectional"))
      (node (ref "J1") (pin "39") (pinfunction "3V3_39") (pintype "bidirectional"))
      (node (ref "J1") (pin "41") (pinfunction "3V3_41") (pintype "bidirectional"))
      (node (ref "J1") (pin "52") (pinfunction "3V3_52") (pintype "bidirectional"))
      (node (ref "P7") (pin "P$1") (pinfunction "P$1_P$1") (pintype "bidirectional"))
      (node (ref "Q1") (pin "2") (pinfunction "S_2") (pintype "passive"))
      (node (ref "R17") (pin "2") (pinfunction "2_2") (pintype "passive"))
      (node (ref "R44") (pin "2") (pinfunction "2_2") (pintype "passive"))
      (node (ref "R46") (pin "2") (pinfunction "2_2") (pintype "passive"))
      (node (ref "R47") (pin "2") (pinfunction "2_2") (pintype "passive"))
      (node (ref "R48") (pin "2") (pinfunction "2_2") (pintype "passive"))
      (node (ref "R51") (pin "1") (pinfunction "1_1") (pintype "passive"))
      (node (ref "R57") (pin "2") (pinfunction "2_2") (pintype "passive"))
      (node (ref "U10") (pin "3") (pinfunction "VDD_3") (pintype "bidirectional"))
      (node (ref "U11") (pin "1") (pinfunction "EN_1") (pintype "bidirectional"))
      (node (ref "U11") (pin "4") (pinfunction "VIN_4") (pintype "bidirectional"))
      (node (ref "U9") (pin "1") (pinfunction "VDD_1") (pintype "passive"))
      (node (ref "U9") (pin "17") (pinfunction "VDD_17") (pintype "power_in"))
      (node (ref "U9") (pin "5") (pinfunction "VDDA_5") (pintype "power_in"))
    )
    (net (code "7") (name "CONFIG_OK") (class "Default")
      (node (ref "R22") (pin "1") (pinfunction "1_1") (pintype "passive"))
      (node (ref "U1") (pin "66") (pinfunction "GPIO[0]_66") (pintype "passive"))
    )
    (net (code "8") (name "CSD") (class "Default")
      (node (ref "C51") (pin "1") (pinfunction "1_1") (pintype "passive"))
      (node (ref "R33") (pin "2") (pinfunction "2_2") (pintype "passive"))
      (node (ref "U6") (pin "4") (pinfunction "CSD_4") (pintype "input"))
    )
    (net (code "9") (name "D+") (class "Default")
      (node (ref "J1") (pin "38") (pinfunction "38_38") (pintype "bidirectional"))
      (node (ref "P2") (pin "P$1") (pinfunction "P$1_P$1") (pintype "bidirectional"))
      (node (ref "R9") (pin "1") (pinfunction "1_1") (pintype "passive"))
    )
    (net (code "10") (name "D-") (class "Default")
      (node (ref "J1") (pin "36") (pinfunction "36_36") (pintype "bidirectional"))
      (node (ref "P1") (pin "P$1") (pinfunction "P$1_P$1") (pintype "bidirectional"))
      (node (ref "R7") (pin "1") (pinfunction "1_1") (pintype "passive"))
    )
    (net (code "11") (name "GPIO6") (class "Default")
      (node (ref "U1") (pin "57") (pinfunction "GPIO[6]_57") (pintype "passive"))
    )
    (net (code "12") (name "GPIO9") (class "Default")
      (node (ref "U1") (pin "52") (pinfunction "GPIO[9]_52") (pintype "passive"))
    )
    (net (code "13") (name "HOST_CSN") (class "Default")
      (node (ref "P12") (pin "P$1") (pinfunction "P$1_P$1") (pintype "bidirectional"))
      (node (ref "R1") (pin "1") (pinfunction "1_1") (pintype "passive"))
      (node (ref "R13") (pin "1") (pinfunction "1_1") (pintype "passive"))
      (node (ref "U1") (pin "1") (pinfunction "HOST_CSN_1") (pintype "passive"))
      (node (ref "U9") (pin "10") (pinfunction "PA4_10") (pintype "bidirectional"))
    )
    (net (code "14") (name "HOST_MISO") (class "Default")
      (node (ref "P10") (pin "P$1") (pinfunction "P$1_P$1") (pintype "bidirectional"))
      (node (ref "R11") (pin "1") (pinfunction "1_1") (pintype "passive"))
      (node (ref "R2") (pin "2") (pinfunction "2_2") (pintype "passive"))
      (node (ref "R38") (pin "1") (pinfunction "1_1") (pintype "passive"))
      (node (ref "U9") (pin "12") (pinfunction "PA6_12") (pintype "bidirectional"))
    )
    (net (code "15") (name "HOST_MOSI") (class "Default")
      (node (ref "P11") (pin "P$1") (pinfunction "P$1_P$1") (pintype "bidirectional"))
      (node (ref "R12") (pin "1") (pinfunction "1_1") (pintype "passive"))
      (node (ref "U1") (pin "3") (pinfunction "HOST_MOSI_3") (pintype "passive"))
      (node (ref "U8") (pin "17") (pinfunction "MOSI_17") (pintype "bidirectional"))
      (node (ref "U9") (pin "13") (pinfunction "PA7_13") (pintype "bidirectional"))
    )
    (net (code "16") (name "HOST_SCK") (class "Default")
      (node (ref "P9") (pin "P$1") (pinfunction "P$1_P$1") (pintype "bidirectional"))
      (node (ref "R10") (pin "1") (pinfunction "1_1") (pintype "passive"))
      (node (ref "U1") (pin "4") (pinfunction "HOST_SCK_4") (pintype "passive"))
      (node (ref "U8") (pin "18") (pinfunction "SCK_18") (pintype "bidirectional"))
      (node (ref "U9") (pin "11") (pinfunction "PA5_11") (pintype "input"))
    )
    (net (code "17") (name "I2C_SCL") (class "Default")
      (node (ref "J1") (pin "30") (pinfunction "30_30") (pintype "bidirectional"))
      (node (ref "P16") (pin "P$1") (pinfunction "P$1_P$1") (pintype "bidirectional"))
      (node (ref "R47") (pin "1") (pinfunction "1_1") (pintype "passive"))
      (node (ref "U10") (pin "1") (pinfunction "SCL_1") (pintype "passive"))
      (node (ref "U9") (pin "29") (pinfunction "PB6_29") (pintype "bidirectional"))
    )
    (net (code "18") (name "I2C_SDA") (class "Default")
      (node (ref "J1") (pin "32") (pinfunction "32_32") (pintype "bidirectional"))
      (node (ref "P19") (pin "P$1") (pinfunction "P$1_P$1") (pintype "bidirectional"))
      (node (ref "R46") (pin "1") (pinfunction "1_1") (pintype "passive"))
      (node (ref "U10") (pin "6") (pinfunction "SDA_6") (pintype "bidirectional"))
      (node (ref "U9") (pin "30") (pinfunction "PB7_30") (pintype "bidirectional"))
    )
    (net (code "19") (name "MCU_NRESET") (class "Default")
      (node (ref "C80") (pin "2") (pinfunction "2_2") (pintype "passive"))
      (node (ref "P6") (pin "P$1") (pinfunction "P$1_P$1") (pintype "bidirectional"))
      (node (ref "R57") (pin "1") (pinfunction "1_1") (pintype "passive"))
      (node (ref "R58") (pin "1") (pinfunction "1_1") (pintype "passive"))
      (node (ref "U9") (pin "4") (pinfunction "NRST_4") (pintype "bidirectional"))
    )
    (net (code "20") (name "Net-(ANT1-SIGNAL)") (class "Default")
      (node (ref "ANT1") (pin "1") (pinfunction "SIGNAL_1") (pintype "bidirectional"))
      (node (ref "C47") (pin "1") (pinfunction "1_1") (pintype "passive"))
      (node (ref "D8") (pin "1") (pinfunction "1_1") (pintype "bidirectional"))
    )
    (net (code "21") (name "Net-(ANT2-SIGNAL)") (class "Default")
      (node (ref "ANT2") (pin "1") (pinfunction "SIGNAL_1") (pintype "bidirectional"))
      (node (ref "C50") (pin "1") (pinfunction "1_1") (pintype "passive"))
      (node (ref "D6") (pin "1") (pinfunction "1_1") (pintype "bidirectional"))
    )
    (net (code "22") (name "Net-(C15-Pad1)") (class "Default")
      (node (ref "C15") (pin "1") (pinfunction "1_1") (pintype "passive"))
      (node (ref "R26") (pin "1") (pinfunction "1_1") (pintype "passive"))
    )
    (net (code "23") (name "Net-(C21-Pad1)") (class "Default")
      (node (ref "C21") (pin "1") (pinfunction "1_1") (pintype "passive"))
      (node (ref "R28") (pin "1") (pinfunction "1_1") (pintype "passive"))
    )
    (net (code "24") (name "Net-(C28-Pad1)") (class "Default")
      (node (ref "C28") (pin "1") (pinfunction "1_1") (pintype "passive"))
      (node (ref "C29") (pin "1") (pinfunction "1_1") (pintype "passive"))
      (node (ref "C30") (pin "1") (pinfunction "1_1") (pintype "passive"))
      (node (ref "L8") (pin "2") (pinfunction "2_2") (pintype "passive"))
    )
    (net (code "25") (name "Net-(C30-Pad2)") (class "Default")
      (node (ref "C30") (pin "2") (pinfunction "2_2") (pintype "passive"))
      (node (ref "L9") (pin "1") (pinfunction "1_1") (pintype "passive"))
    )
    (net (code "26") (name "Net-(C40-Pad2)") (class "Default")
      (node (ref "C40") (pin "2") (pinfunction "2_2") (pintype "passive"))
      (node (ref "C41") (pin "2") (pinfunction "2_2") (pintype "passive"))
      (node (ref "L12") (pin "2") (pinfunction "2_2") (pintype "passive"))
      (node (ref "L13") (pin "1") (pinfunction "1_1") (pintype "passive"))
    )
    (net (code "27") (name "Net-(C44-Pad2)") (class "Default")
      (node (ref "C44") (pin "2") (pinfunction "2_2") (pintype "passive"))
      (node (ref "C45") (pin "1") (pinfunction "1_1") (pintype "passive"))
      (node (ref "L14") (pin "2") (pinfunction "2_2") (pintype "passive"))
      (node (ref "L15") (pin "1") (pinfunction "1_1") (pintype "passive"))
    )
    (net (code "28") (name "Net-(C46-Pad2)") (class "Default")
      (node (ref "C46") (pin "2") (pinfunction "2_2") (pintype "passive"))
      (node (ref "C47") (pin "2") (pinfunction "2_2") (pintype "passive"))
      (node (ref "L15") (pin "2") (pinfunction "2_2") (pintype "passive"))
    )
    (net (code "29") (name "Net-(C48-Pad2)") (class "Default")
      (node (ref "C48") (pin "2") (pinfunction "2_2") (pintype "passive"))
      (node (ref "L16") (pin "1") (pinfunction "1_1") (pintype "passive"))
      (node (ref "R32") (pin "2") (pinfunction "2_2") (pintype "passive"))
    )
    (net (code "30") (name "Net-(C49-Pad2)") (class "Default")
      (node (ref "C49") (pin "2") (pinfunction "2_2") (pintype "passive"))
      (node (ref "C50") (pin "2") (pinfunction "2_2") (pintype "passive"))
      (node (ref "L16") (pin "2") (pinfunction "2_2") (pintype "passive"))
    )
    (net (code "31") (name "Net-(C55-Pad1)") (class "Default")
      (node (ref "C55") (pin "1") (pinfunction "1_1") (pintype "passive"))
      (node (ref "R37") (pin "1") (pinfunction "1_1") (pintype "passive"))
    )
    (net (code "32") (name "Net-(C59-Pad1)") (class "Default")
      (node (ref "C59") (pin "1") (pinfunction "1_1") (pintype "passive"))
      (node (ref "C60") (pin "2") (pinfunction "2_2") (pintype "passive"))
      (node (ref "C61") (pin "2") (pinfunction "2_2") (pintype "passive"))
    )
    (net (code "33") (name "Net-(C63-Pad1)") (class "Default")
      (node (ref "C63") (pin "1") (pinfunction "1_1") (pintype "passive"))
      (node (ref "R54") (pin "1") (pinfunction "1_1") (pintype "passive"))
    )
    (net (code "34") (name "Net-(D1-+)") (class "Default")
      (node (ref "D1") (pin "1") (pinfunction "+_1") (pintype "passive"))
      (node (ref "R21") (pin "2") (pinfunction "2_2") (pintype "passive"))
    )
    (net (code "35") (name "Net-(D2-+)") (class "Default")
      (node (ref "D2") (pin "1") (pinfunction "+_1") (pintype "passive"))
      (node (ref "R22") (pin "2") (pinfunction "2_2") (pintype "passive"))
    )
    (net (code "36") (name "Net-(D3-+)") (class "Default")
      (node (ref "D3") (pin "1") (pinfunction "+_1") (pintype "passive"))
      (node (ref "R23") (pin "2") (pinfunction "2_2") (pintype "passive"))
    )
    (net (code "37") (name "Net-(D5-+)") (class "Default")
      (node (ref "D5") (pin "1") (pinfunction "+_1") (pintype "passive"))
      (node (ref "R51") (pin "2") (pinfunction "2_2") (pintype "passive"))
    )
    (net (code "38") (name "Net-(J1-Pad45)") (class "Default")
      (node (ref "J1") (pin "45") (pinfunction "45_45") (pintype "bidirectional"))
      (node (ref "R10") (pin "2") (pinfunction "2_2") (pintype "passive"))
    )
    (net (code "39") (name "Net-(J1-Pad47)") (class "Default")
      (node (ref "J1") (pin "47") (pinfunction "47_47") (pintype "bidirectional"))
      (node (ref "R11") (pin "2") (pinfunction "2_2") (pintype "passive"))
    )
    (net (code "40") (name "Net-(J1-Pad49)") (class "Default")
      (node (ref "J1") (pin "49") (pinfunction "49_49") (pintype "bidirectional"))
      (node (ref "R12") (pin "2") (pinfunction "2_2") (pintype "passive"))
    )
    (net (code "41") (name "Net-(J1-Pad51)") (class "Default")
      (node (ref "J1") (pin "51") (pinfunction "51_51") (pintype "bidirectional"))
      (node (ref "R13") (pin "2") (pinfunction "2_2") (pintype "passive"))
    )
    (net (code "42") (name "Net-(Q1-G)") (class "Default")
      (node (ref "Q1") (pin "1") (pinfunction "G_1") (pintype "passive"))
      (node (ref "Q2") (pin "3") (pinfunction "D_3") (pintype "passive"))
      (node (ref "R17") (pin "1") (pinfunction "1_1") (pintype "passive"))
    )
    (net (code "43") (name "Net-(Q2-G)") (class "Default")
      (node (ref "Q2") (pin "1") (pinfunction "G_1") (pintype "passive"))
      (node (ref "R18") (pin "1") (pinfunction "1_1") (pintype "passive"))
      (node (ref "R52") (pin "1") (pinfunction "1_1") (pintype "passive"))
    )
    (net (code "44") (name "Net-(U1-HOST_MISO)") (class "Default")
      (node (ref "R2") (pin "1") (pinfunction "1_1") (pintype "passive"))
      (node (ref "U1") (pin "2") (pinfunction "HOST_MISO_2") (pintype "passive"))
    )
    (net (code "45") (name "Net-(U1-RADIO_A_CLK_I)") (class "Default")
      (node (ref "R14") (pin "1") (pinfunction "1_1") (pintype "passive"))
      (node (ref "U1") (pin "43") (pinfunction "RADIO_A_CLK_I_43") (pintype "passive"))
    )
    (net (code "46") (name "Net-(U1-RADIO_B_CLK_I)") (class "Default")
      (node (ref "R8") (pin "1") (pinfunction "1_1") (pintype "passive"))
      (node (ref "U1") (pin "34") (pinfunction "RADIO_B_CLK_I_34") (pintype "passive"))
    )
    (net (code "47") (name "Net-(U2-DCC_SW)") (class "Default")
      (node (ref "L1") (pin "2") (pinfunction "2_2") (pintype "passive"))
      (node (ref "U2") (pin "8") (pinfunction "DCC_SW_8") (pintype "bidirectional"))
    )
    (net (code "48") (name "Net-(U2-RFI_N)") (class "Default")
      (node (ref "C19") (pin "2") (pinfunction "2_2") (pintype "passive"))
      (node (ref "L3") (pin "2") (pinfunction "2_2") (pintype "passive"))
      (node (ref "U2") (pin "23") (pinfunction "RFI_N_23") (pintype "bidirectional"))
    )
    (net (code "49") (name "Net-(U2-RFI_P)") (class "Default")
      (node (ref "C18") (pin "2") (pinfunction "2_2") (pintype "passive"))
      (node (ref "L3") (pin "1") (pinfunction "1_1") (pintype "passive"))
      (node (ref "U2") (pin "22") (pinfunction "RFI_P_22") (pintype "bidirectional"))
    )
    (net (code "50") (name "Net-(U2-VDD_IN)") (class "Default")
      (node (ref "C14") (pin "1") (pinfunction "1_1") (pintype "passive"))
      (node (ref "L2") (pin "2") (pinfunction "2_2") (pintype "passive"))
      (node (ref "R25") (pin "1") (pinfunction "1_1") (pintype "passive"))
      (node (ref "U2") (pin "2") (pinfunction "VDD_IN_2") (pintype "bidirectional"))
    )
    (net (code "51") (name "Net-(U2-VREG)") (class "Default")
      (node (ref "C16") (pin "1") (pinfunction "1_1") (pintype "passive"))
      (node (ref "L1") (pin "1") (pinfunction "1_1") (pintype "passive"))
      (node (ref "L2") (pin "1") (pinfunction "1_1") (pintype "passive"))
      (node (ref "U2") (pin "6") (pinfunction "VREG_6") (pintype "bidirectional"))
    )
    (net (code "52") (name "Net-(U2-XTA)") (class "Default")
      (node (ref "C15") (pin "2") (pinfunction "2_2") (pintype "passive"))
      (node (ref "U2") (pin "3") (pinfunction "XTA_3") (pintype "bidirectional"))
    )
    (net (code "53") (name "Net-(U3-DCC_SW)") (class "Default")
      (node (ref "L4") (pin "2") (pinfunction "2_2") (pintype "passive"))
      (node (ref "U3") (pin "8") (pinfunction "DCC_SW_8") (pintype "bidirectional"))
    )
    (net (code "54") (name "Net-(U3-RFI_N)") (class "Default")
      (node (ref "C25") (pin "2") (pinfunction "2_2") (pintype "passive"))
      (node (ref "L6") (pin "2") (pinfunction "2_2") (pintype "passive"))
      (node (ref "U3") (pin "23") (pinfunction "RFI_N_23") (pintype "bidirectional"))
    )
    (net (code "55") (name "Net-(U3-RFI_P)") (class "Default")
      (node (ref "C24") (pin "2") (pinfunction "2_2") (pintype "passive"))
      (node (ref "L6") (pin "1") (pinfunction "1_1") (pintype "passive"))
      (node (ref "U3") (pin "22") (pinfunction "RFI_P_22") (pintype "bidirectional"))
    )
    (net (code "56") (name "Net-(U3-RFO)") (class "Default")
      (node (ref "C28") (pin "2") (pinfunction "2_2") (pintype "passive"))
      (node (ref "L7") (pin "1") (pinfunction "1_1") (pintype "passive"))
      (node (ref "L8") (pin "1") (pinfunction "1_1") (pintype "passive"))
      (node (ref "U3") (pin "24") (pinfunction "RFO_24") (pintype "bidirectional"))
    )
    (net (code "57") (name "Net-(U3-VDD_IN)") (class "Default")
      (node (ref "C20") (pin "1") (pinfunction "1_1") (pintype "passive"))
      (node (ref "L5") (pin "2") (pinfunction "2_2") (pintype "passive"))
      (node (ref "R27") (pin "1") (pinfunction "1_1") (pintype "passive"))
      (node (ref "U3") (pin "2") (pinfunction "VDD_IN_2") (pintype "bidirectional"))
    )
    (net (code "58") (name "Net-(U3-VREG)") (class "Default")
      (node (ref "C22") (pin "1") (pinfunction "1_1") (pintype "passive"))
      (node (ref "L4") (pin "1") (pinfunction "1_1") (pintype "passive"))
      (node (ref "L5") (pin "1") (pinfunction "1_1") (pintype "passive"))
      (node (ref "U3") (pin "6") (pinfunction "VREG_6") (pintype "bidirectional"))
    )
    (net (code "59") (name "Net-(U3-XTA)") (class "Default")
      (node (ref "C21") (pin "2") (pinfunction "2_2") (pintype "passive"))
      (node (ref "U3") (pin "3") (pinfunction "XTA_3") (pintype "bidirectional"))
    )
    (net (code "60") (name "Net-(U4-IN{slash}OUT)") (class "Default")
      (node (ref "C34") (pin "1") (pinfunction "1_1") (pintype "passive"))
      (node (ref "U4") (pin "2") (pinfunction "IN/OUT_2") (pintype "bidirectional"))
    )
    (net (code "61") (name "Net-(U4-OUT{slash}IN)") (class "Default")
      (node (ref "C19") (pin "1") (pinfunction "1_1") (pintype "passive"))
      (node (ref "C25") (pin "1") (pinfunction "1_1") (pintype "passive"))
      (node (ref "C61") (pin "1") (pinfunction "1_1") (pintype "passive"))
      (node (ref "U4") (pin "5") (pinfunction "OUT/IN_5") (pintype "bidirectional"))
    )
    (net (code "62") (name "Net-(U5-IN{slash}OUT)") (class "Default")
      (node (ref "R31") (pin "2") (pinfunction "2_2") (pintype "passive"))
      (node (ref "R32") (pin "1") (pinfunction "1_1") (pintype "passive"))
      (node (ref "U5") (pin "2") (pinfunction "IN/OUT_2") (pintype "bidirectional"))
    )
    (net (code "63") (name "Net-(U5-OUT{slash}IN)") (class "Default")
      (node (ref "U5") (pin "5") (pinfunction "OUT/IN_5") (pintype "bidirectional"))
      (node (ref "U6") (pin "7") (pinfunction "LNA_IN_7") (pintype "passive"))
    )
    (net (code "64") (name "Net-(U6-ANT)") (class "Default")
      (node (ref "C43") (pin "2") (pinfunction "2_2") (pintype "passive"))
      (node (ref "C45") (pin "2") (pinfunction "2_2") (pintype "passive"))
      (node (ref "L14") (pin "1") (pinfunction "1_1") (pintype "passive"))
      (node (ref "U6") (pin "9") (pinfunction "ANT_9") (pintype "passive"))
    )
    (net (code "65") (name "Net-(U6-PA_OUT)") (class "Default")
      (node (ref "L11") (pin "1") (pinfunction "1_1") (pintype "passive"))
      (node (ref "L12") (pin "1") (pinfunction "1_1") (pintype "passive"))
      (node (ref "U6") (pin "13") (pinfunction "PA_OUT_13") (pintype "passive"))
    )
    (net (code "66") (name "Net-(U6-RX)") (class "Default")
      (node (ref "C34") (pin "2") (pinfunction "2_2") (pintype "passive"))
      (node (ref "U6") (pin "2") (pinfunction "RX_2") (pintype "passive"))
    )
    (net (code "67") (name "Net-(U6-RX_FLT)") (class "Default")
      (node (ref "R31") (pin "1") (pinfunction "1_1") (pintype "passive"))
      (node (ref "U6") (pin "8") (pinfunction "RX_FLT_8") (pintype "passive"))
    )
    (net (code "68") (name "Net-(U6-TX)") (class "Default")
      (node (ref "C33") (pin "2") (pinfunction "2_2") (pintype "passive"))
      (node (ref "U6") (pin "1") (pinfunction "TX_1") (pintype "passive"))
    )
    (net (code "69") (name "Net-(U6-TX_IN)") (class "Default")
      (node (ref "C42") (pin "2") (pinfunction "2_2") (pintype "passive"))
      (node (ref "L13") (pin "2") (pinfunction "2_2") (pintype "passive"))
      (node (ref "U6") (pin "11") (pinfunction "TX_IN_11") (pintype "passive"))
    )
    (net (code "70") (name "Net-(U6-VCC1)") (class "Default")
      (node (ref "L10") (pin "1") (pinfunction "1_1") (pintype "passive"))
      (node (ref "U6") (pin "16") (pinfunction "VCC1_16") (pintype "power_in"))
    )
    (net (code "71") (name "Net-(U8-DCC_SW)") (class "Default")
      (node (ref "L18") (pin "2") (pinfunction "2_2") (pintype "passive"))
      (node (ref "U8") (pin "9") (pinfunction "DCC_SW_9") (pintype "bidirectional"))
    )
    (net (code "72") (name "Net-(U8-MISO)") (class "Default")
      (node (ref "R38") (pin "2") (pinfunction "2_2") (pintype "passive"))
      (node (ref "U8") (pin "16") (pinfunction "MISO_16") (pintype "bidirectional"))
    )
    (net (code "73") (name "Net-(U8-NSS)") (class "Default")
      (node (ref "R41") (pin "2") (pinfunction "2_2") (pintype "passive"))
      (node (ref "U8") (pin "19") (pinfunction "NSS_19") (pintype "bidirectional"))
    )
    (net (code "74") (name "Net-(U8-RFI_N)") (class "Default")
      (node (ref "C59") (pin "2") (pinfunction "2_2") (pintype "passive"))
      (node (ref "L19") (pin "2") (pinfunction "2_2") (pintype "passive"))
      (node (ref "U8") (pin "22") (pinfunction "RFI_N_22") (pintype "bidirectional"))
    )
    (net (code "75") (name "Net-(U8-RFI_P)") (class "Default")
      (node (ref "C58") (pin "2") (pinfunction "2_2") (pintype "passive"))
      (node (ref "L19") (pin "1") (pinfunction "1_1") (pintype "passive"))
      (node (ref "U8") (pin "21") (pinfunction "RFI_P_21") (pintype "bidirectional"))
    )
    (net (code "76") (name "Net-(U8-VDD_IN)") (class "Default")
      (node (ref "C54") (pin "1") (pinfunction "1_1") (pintype "passive"))
      (node (ref "L17") (pin "2") (pinfunction "2_2") (pintype "passive"))
      (node (ref "R36") (pin "1") (pinfunction "1_1") (pintype "passive"))
      (node (ref "U8") (pin "1") (pinfunction "VDD_IN_1") (pintype "bidirectional"))
    )
    (net (code "77") (name "Net-(U8-VREG)") (class "Default")
      (node (ref "C56") (pin "1") (pinfunction "1_1") (pintype "passive"))
      (node (ref "L17") (pin "1") (pinfunction "1_1") (pintype "passive"))
      (node (ref "L18") (pin "1") (pinfunction "1_1") (pintype "passive"))
      (node (ref "U8") (pin "7") (pinfunction "VREG_7") (pintype "bidirectional"))
    )
    (net (code "78") (name "Net-(U8-XTA)") (class "Default")
      (node (ref "C55") (pin "2") (pinfunction "2_2") (pintype "passive"))
      (node (ref "U8") (pin "3") (pinfunction "XTA_3") (pintype "bidirectional"))
    )
    (net (code "79") (name "Net-(U9-BOOT)") (class "Default")
      (node (ref "R44") (pin "1") (pinfunction "1_1") (pintype "passive"))
      (node (ref "R45") (pin "2") (pinfunction "2_2") (pintype "passive"))
      (node (ref "U9") (pin "31") (pinfunction "BOOT_31") (pintype "bidirectional"))
    )
    (net (code "80") (name "Net-(U9-PA0-CK_IN)") (class "Default")
      (node (ref "R42") (pin "2") (pinfunction "2_2") (pintype "passive"))
      (node (ref "R43") (pin "1") (pinfunction "1_1") (pintype "passive"))
      (node (ref "U9") (pin "6") (pinfunction "PA0-CK_IN_6") (pintype "bidirectional"))
    )
    (net (code "81") (name "Net-(U9-PC14-OSC32_IN)") (class "Default")
      (node (ref "C66") (pin "2") (pinfunction "2_2") (pintype "passive"))
      (node (ref "U9") (pin "2") (pinfunction "PC14-OSC32_IN_2") (pintype "bidirectional"))
      (node (ref "Y1") (pin "2") (pinfunction "2_2") (pintype "bidirectional"))
    )
    (net (code "82") (name "Net-(U9-PC15-OSC32_OUT)") (class "Default")
      (node (ref "C67") (pin "1") (pinfunction "1_1") (pintype "passive"))
      (node (ref "U9") (pin "3") (pinfunction "PC15-OSC32_OUT_3") (pintype "bidirectional"))
      (node (ref "Y1") (pin "1") (pinfunction "1_1") (pintype "bidirectional"))
    )
    (net (code "83") (name "Net-(U10-\\E\\V\\E\\N\\T\\)") (class "Default")
      (node (ref "R48") (pin "1") (pinfunction "1_1") (pintype "passive"))
      (node (ref "U10") (pin "2") (pinfunction "\\E\\V\\E\\N\\T\\_2") (pintype "passive"))
    )
    (net (code "84") (name "Net-(U11-FB)") (class "Default")
      (node (ref "R49") (pin "2") (pinfunction "2_2") (pintype "passive"))
      (node (ref "R50") (pin "1") (pinfunction "1_1") (pintype "passive"))
      (node (ref "U11") (pin "5") (pinfunction "FB_5") (pintype "bidirectional"))
    )
    (net (code "85") (name "Net-(U11-SW)") (class "Default")
      (node (ref "L20") (pin "1") (pinfunction "1_1") (pintype "passive"))
      (node (ref "U11") (pin "3") (pinfunction "SW_3") (pintype "bidirectional"))
    )
    (net (code "86") (name "Net-(U12-IN{slash}OUT)") (class "Default")
      (node (ref "C31") (pin "1") (pinfunction "1_1") (pintype "passive"))
      (node (ref "L9") (pin "2") (pinfunction "2_2") (pintype "passive"))
      (node (ref "U12") (pin "2") (pinfunction "IN/OUT_2") (pintype "bidirectional"))
    )
    (net (code "87") (name "Net-(U12-OUT{slash}IN)") (class "Default")
      (node (ref "C33") (pin "1") (pinfunction "1_1") (pintype "passive"))
      (node (ref "U12") (pin "5") (pinfunction "OUT/IN_5") (pintype "bidirectional"))
    )
    (net (code "88") (name "Net-(Y2-OUT)") (class "Default")
      (node (ref "R24") (pin "1") (pinfunction "1_1") (pintype "passive"))
      (node (ref "Y2") (pin "3") (pinfunction "OUT_3") (pintype "bidirectional"))
    )
    (net (code "89") (name "Net-(Y2-VCC)") (class "Default")
      (node (ref "C13") (pin "2") (pinfunction "2_2") (pintype "passive"))
      (node (ref "FB1") (pin "2") (pinfunction "2_2") (pintype "passive"))
      (node (ref "Y2") (pin "4") (pinfunction "VCC_4") (pintype "bidirectional"))
    )
    (net (code "90") (name "PA_ON") (class "Default")
      (node (ref "C53") (pin "1") (pinfunction "1_1") (pintype "passive"))
      (node (ref "R35") (pin "2") (pinfunction "2_2") (pintype "passive"))
      (node (ref "U6") (pin "5") (pinfunction "CPS_5") (pintype "input"))
    )
    (net (code "91") (name "POWER_EN") (class "Default")
      (node (ref "U9") (pin "7") (pinfunction "PA1_7") (pintype "bidirectional"))
    )
    (net (code "92") (name "POWER_GND") (class "Default")
      (node (ref "ANT1") (pin "2") (pinfunction "GND_2") (pintype "bidirectional"))
      (node (ref "ANT1") (pin "3") (pinfunction "GND_3") (pintype "bidirectional"))
      (node (ref "ANT2") (pin "2") (pinfunction "GND_2") (pintype "bidirectional"))
      (node (ref "ANT2") (pin "3") (pinfunction "GND_3") (pintype "bidirectional"))
      (node (ref "C1") (pin "1") (pinfunction "1_1") (pintype "passive"))
      (node (ref "C10") (pin "1") (pinfunction "1_1") (pintype "passive"))
      (node (ref "C11") (pin "1") (pinfunction "1_1") (pintype "passive"))
      (node (ref "C12") (pin "1") (pinfunction "1_1") (pintype "passive"))
      (node (ref "C13") (pin "1") (pinfunction "1_1") (pintype "passive"))
      (node (ref "C14") (pin "2") (pinfunction "2_2") (pintype "passive"))
      (node (ref "C16") (pin "2") (pinfunction "2_2") (pintype "passive"))
      (node (ref "C17") (pin "1") (pinfunction "1_1") (pintype "passive"))
      (node (ref "C18") (pin "1") (pinfunction "1_1") (pintype "passive"))
      (node (ref "C2") (pin "1") (pinfunction "1_1") (pintype "passive"))
      (node (ref "C20") (pin "2") (pinfunction "2_2") (pintype "passive"))
      (node (ref "C22") (pin "2") (pinfunction "2_2") (pintype "passive"))
      (node (ref "C23") (pin "1") (pinfunction "1_1") (pintype "passive"))
      (node (ref "C24") (pin "1") (pinfunction "1_1") (pintype "passive"))
      (node (ref "C26") (pin "2") (pinfunction "2_2") (pintype "passive"))
      (node (ref "C27") (pin "2") (pinfunction "2_2") (pintype "passive"))
      (node (ref "C29") (pin "2") (pinfunction "2_2") (pintype "passive"))
      (node (ref "C3") (pin "1") (pinfunction "1_1") (pintype "passive"))
      (node (ref "C31") (pin "2") (pinfunction "2_2") (pintype "passive"))
      (node (ref "C35") (pin "1") (pinfunction "1_1") (pintype "passive"))
      (node (ref "C36") (pin "1") (pinfunction "1_1") (pintype "passive"))
      (node (ref "C37") (pin "1") (pinfunction "1_1") (pintype "passive"))
      (node (ref "C38") (pin "1") (pinfunction "1_1") (pintype "passive"))
      (node (ref "C39") (pin "1") (pinfunction "1_1") (pintype "passive"))
      (node (ref "C4") (pin "1") (pinfunction "1_1") (pintype "passive"))
      (node (ref "C40") (pin "1") (pinfunction "1_1") (pintype "passive"))
      (node (ref "C41") (pin "1") (pinfunction "1_1") (pintype "passive"))
      (node (ref "C42") (pin "1") (pinfunction "1_1") (pintype "passive"))
      (node (ref "C43") (pin "1") (pinfunction "1_1") (pintype "passive"))
      (node (ref "C44") (pin "1") (pinfunction "1_1") (pintype "passive"))
      (node (ref "C46") (pin "1") (pinfunction "1_1") (pintype "passive"))
      (node (ref "C48") (pin "1") (pinfunction "1_1") (pintype "passive"))
      (node (ref "C49") (pin "1") (pinfunction "1_1") (pintype "passive"))
      (node (ref "C5") (pin "1") (pinfunction "1_1") (pintype "passive"))
      (node (ref "C51") (pin "2") (pinfunction "2_2") (pintype "passive"))
      (node (ref "C52") (pin "2") (pinfunction "2_2") (pintype "passive"))
      (node (ref "C53") (pin "2") (pinfunction "2_2") (pintype "passive"))
      (node (ref "C54") (pin "2") (pinfunction "2_2") (pintype "passive"))
      (node (ref "C56") (pin "2") (pinfunction "2_2") (pintype "passive"))
      (node (ref "C57") (pin "1") (pinfunction "1_1") (pintype "passive"))
      (node (ref "C58") (pin "1") (pinfunction "1_1") (pintype "passive"))
      (node (ref "C6") (pin "1") (pinfunction "1_1") (pintype "passive"))
      (node (ref "C60") (pin "1") (pinfunction "1_1") (pintype "passive"))
      (node (ref "C62") (pin "1") (pinfunction "1_1") (pintype "passive"))
      (node (ref "C64") (pin "1") (pinfunction "1_1") (pintype "passive"))
      (node (ref "C65") (pin "1") (pinfunction "1_1") (pintype "passive"))
      (node (ref "C66") (pin "1") (pinfunction "1_1") (pintype "passive"))
      (node (ref "C67") (pin "2") (pinfunction "2_2") (pintype "passive"))
      (node (ref "C68") (pin "1") (pinfunction "1_1") (pintype "passive"))
      (node (ref "C69") (pin "1") (pinfunction "1_1") (pintype "passive"))
      (node (ref "C7") (pin "1") (pinfunction "1_1") (pintype "passive"))
      (node (ref "C71") (pin "1") (pinfunction "1_1") (pintype "passive"))
      (node (ref "C72") (pin "1") (pinfunction "1_1") (pintype "passive"))
      (node (ref "C73") (pin "1") (pinfunction "1_1") (pintype "passive"))
      (node (ref "C74") (pin "1") (pinfunction "1_1") (pintype "passive"))
      (node (ref "C75") (pin "1") (pinfunction "1_1") (pintype "passive"))
      (node (ref "C76") (pin "1") (pinfunction "1_1") (pintype "passive"))
      (node (ref "C77") (pin "1") (pinfunction "1_1") (pintype "passive"))
      (node (ref "C78") (pin "1") (pinfunction "1_1") (pintype "passive"))
      (node (ref "C79") (pin "1") (pinfunction "1_1") (pintype "passive"))
      (node (ref "C8") (pin "1") (pinfunction "1_1") (pintype "passive"))
      (node (ref "C80") (pin "1") (pinfunction "1_1") (pintype "passive"))
      (node (ref "C81") (pin "1") (pinfunction "1_1") (pintype "passive"))
      (node (ref "C82") (pin "1") (pinfunction "1_1") (pintype "passive"))
      (node (ref "C83") (pin "1") (pinfunction "1_1") (pintype "passive"))
      (node (ref "C84") (pin "1") (pinfunction "1_1") (pintype "passive"))
      (node (ref "C9") (pin "1") (pinfunction "1_1") (pintype "passive"))
      (node (ref "D1") (pin "2") (pinfunction "-_2") (pintype "passive"))
      (node (ref "D2") (pin "2") (pinfunction "-_2") (pintype "passive"))
      (node (ref "D3") (pin "2") (pinfunction "-_2") (pintype "passive"))
      (node (ref "D5") (pin "2") (pinfunction "-_2") (pintype "passive"))
      (node (ref "D6") (pin "2") (pinfunction "2_2") (pintype "bidirectional"))
      (node (ref "D8") (pin "2") (pinfunction "2_2") (pintype "bidirectional"))
      (node (ref "J1") (pin "15") (pinfunction "GND_15") (pintype "bidirectional"))
      (node (ref "J1") (pin "18") (pinfunction "GND_18") (pintype "bidirectional"))
      (node (ref "J1") (pin "21") (pinfunction "GND_21") (pintype "bidirectional"))
      (node (ref "J1") (pin "26") (pinfunction "GND_26") (pintype "bidirectional"))
      (node (ref "J1") (pin "27") (pinfunction "GND_27") (pintype "bidirectional"))
      (node (ref "J1") (pin "29") (pinfunction "GND_29") (pintype "bidirectional"))
      (node (ref "J1") (pin "34") (pinfunction "GND_34") (pintype "bidirectional"))
      (node (ref "J1") (pin "35") (pinfunction "GND_35") (pintype "bidirectional"))
      (node (ref "J1") (pin "37") (pinfunction "GND_37") (pintype "bidirectional"))
      (node (ref "J1") (pin "4") (pinfunction "GND_4") (pintype "bidirectional"))
      (node (ref "J1") (pin "40") (pinfunction "GND_40") (pintype "bidirectional"))
      (node (ref "J1") (pin "43") (pinfunction "GND_43") (pintype "bidirectional"))
      (node (ref "J1") (pin "50") (pinfunction "GND_50") (pintype "bidirectional"))
      (node (ref "J1") (pin "9") (pinfunction "GND_9") (pintype "bidirectional"))
      (node (ref "J10") (pin "1") (pinfunction "1_1") (pintype "bidirectional"))
      (node (ref "J10") (pin "2") (pinfunction "2_2") (pintype "bidirectional"))
      (node (ref "J10") (pin "3") (pinfunction "3_3") (pintype "bidirectional"))
      (node (ref "J11") (pin "1") (pinfunction "P$1_1") (pintype "bidirectional"))
      (node (ref "J17") (pin "1") (pinfunction "1_1") (pintype "bidirectional"))
      (node (ref "J17") (pin "2") (pinfunction "2_2") (pintype "bidirectional"))
      (node (ref "J17") (pin "3") (pinfunction "3_3") (pintype "bidirectional"))
      (node (ref "J2") (pin "1") (pinfunction "P$1_1") (pintype "bidirectional"))
      (node (ref "J3") (pin "1") (pinfunction "1_1") (pintype "bidirectional"))
      (node (ref "J3") (pin "2") (pinfunction "2_2") (pintype "bidirectional"))
      (node (ref "J3") (pin "3") (pinfunction "3_3") (pintype "bidirectional"))
      (node (ref "J4") (pin "1") (pinfunction "1_1") (pintype "bidirectional"))
      (node (ref "J4") (pin "2") (pinfunction "2_2") (pintype "bidirectional"))
      (node (ref "J4") (pin "3") (pinfunction "3_3") (pintype "bidirectional"))
      (node (ref "J5") (pin "1") (pinfunction "1_1") (pintype "bidirectional"))
      (node (ref "J5") (pin "2") (pinfunction "2_2") (pintype "bidirectional"))
      (node (ref "J5") (pin "3") (pinfunction "3_3") (pintype "bidirectional"))
      (node (ref "J6") (pin "1") (pinfunction "1_1") (pintype "bidirectional"))
      (node (ref "J6") (pin "2") (pinfunction "2_2") (pintype "bidirectional"))
      (node (ref "J6") (pin "3") (pinfunction "3_3") (pintype "bidirectional"))
      (node (ref "J7") (pin "1") (pinfunction "1_1") (pintype "bidirectional"))
      (node (ref "J7") (pin "2") (pinfunction "2_2") (pintype "bidirectional"))
      (node (ref "J7") (pin "3") (pinfunction "3_3") (pintype "bidirectional"))
      (node (ref "P24") (pin "P$1") (pinfunction "P$1_P$1") (pintype "bidirectional"))
      (node (ref "P8") (pin "P$1") (pinfunction "P$1_P$1") (pintype "bidirectional"))
      (node (ref "Q2") (pin "2") (pinfunction "S_2") (pintype "passive"))
      (node (ref "R15") (pin "1") (pinfunction "1_1") (pintype "passive"))
      (node (ref "R15") (pin "2") (pinfunction "2_2") (pintype "passive"))
      (node (ref "R16") (pin "1") (pinfunction "1_1") (pintype "passive"))
      (node (ref "R16") (pin "2") (pinfunction "2_2") (pintype "passive"))
      (node (ref "R3") (pin "1") (pinfunction "1_1") (pintype "passive"))
      (node (ref "R3") (pin "2") (pinfunction "2_2") (pintype "passive"))
      (node (ref "R43") (pin "2") (pinfunction "2_2") (pintype "passive"))
      (node (ref "R45") (pin "1") (pinfunction "1_1") (pintype "passive"))
      (node (ref "R5") (pin "1") (pinfunction "1_1") (pintype "passive"))
      (node (ref "R50") (pin "2") (pinfunction "2_2") (pintype "passive"))
      (node (ref "R52") (pin "2") (pinfunction "2_2") (pintype "passive"))
      (node (ref "R53") (pin "1") (pinfunction "1_1") (pintype "passive"))
      (node (ref "R53") (pin "2") (pinfunction "2_2") (pintype "passive"))
      (node (ref "U1") (pin "15") (pinfunction "GND_15") (pintype "power_in"))
      (node (ref "U1") (pin "20") (pinfunction "SP_VALID_20") (pintype "passive"))
      (node (ref "U1") (pin "24") (pinfunction "GND_24") (pintype "power_in"))
      (node (ref "U1") (pin "25") (pinfunction "GND_25") (pintype "power_in"))
      (node (ref "U1") (pin "39") (pinfunction "GND_39") (pintype "power_in"))
      (node (ref "U1") (pin "46") (pinfunction "GND_46") (pintype "power_in"))
      (node (ref "U1") (pin "55") (pinfunction "GND_55") (pintype "power_in"))
      (node (ref "U1") (pin "6") (pinfunction "GND_6") (pintype "power_in"))
      (node (ref "U1") (pin "62") (pinfunction "GND_62") (pintype "power_in"))
      (node (ref "U1") (pin "69") (pinfunction "GND_69") (pintype "power_in"))
      (node (ref "U1") (pin "9") (pinfunction "GND_9") (pintype "passive"))
      (node (ref "U10") (pin "4") (pinfunction "ADDR/T\\H\\E\\R\\M\\_4") (pintype "passive"))
      (node (ref "U10") (pin "5") (pinfunction "GND_5") (pintype "bidirectional"))
      (node (ref "U11") (pin "2") (pinfunction "GND_2") (pintype "bidirectional"))
      (node (ref "U12") (pin "1") (pinfunction "GND_1") (pintype "bidirectional"))
      (node (ref "U12") (pin "3") (pinfunction "GND_3") (pintype "bidirectional"))
      (node (ref "U12") (pin "4") (pinfunction "GND_4") (pintype "bidirectional"))
      (node (ref "U12") (pin "6") (pinfunction "GND_6") (pintype "bidirectional"))
      (node (ref "U2") (pin "20") (pinfunction "GND_20") (pintype "bidirectional"))
      (node (ref "U2") (pin "25") (pinfunction "GND_25") (pintype "power_in"))
      (node (ref "U2") (pin "7") (pinfunction "GND_7") (pintype "power_in"))
      (node (ref "U3") (pin "20") (pinfunction "GND_20") (pintype "bidirectional"))
      (node (ref "U3") (pin "25") (pinfunction "GND_25") (pintype "power_in"))
      (node (ref "U3") (pin "7") (pinfunction "GND_7") (pintype "power_in"))
      (node (ref "U4") (pin "1") (pinfunction "GND_1") (pintype "bidirectional"))
      (node (ref "U4") (pin "3") (pinfunction "GND_3") (pintype "bidirectional"))
      (node (ref "U4") (pin "4") (pinfunction "GND_4") (pintype "bidirectional"))
      (node (ref "U4") (pin "6") (pinfunction "GND_6") (pintype "bidirectional"))
      (node (ref "U5") (pin "1") (pinfunction "GND_1") (pintype "bidirectional"))
      (node (ref "U5") (pin "3") (pinfunction "GND_3") (pintype "bidirectional"))
      (node (ref "U5") (pin "4") (pinfunction "GND_4") (pintype "bidirectional"))
      (node (ref "U5") (pin "6") (pinfunction "GND_6") (pintype "bidirectional"))
      (node (ref "U6") (pin "10") (pinfunction "GND_10") (pintype "power_in"))
      (node (ref "U6") (pin "12") (pinfunction "GND_12") (pintype "power_in"))
      (node (ref "U6") (pin "17") (pinfunction "GND_17") (pintype "power_in"))
      (node (ref "U8") (pin "2") (pinfunction "GND_2") (pintype "bidirectional"))
      (node (ref "U8") (pin "20") (pinfunction "GND_20") (pintype "bidirectional"))
      (node (ref "U8") (pin "25") (pinfunction "GND_25") (pintype "bidirectional"))
      (node (ref "U8") (pin "5") (pinfunction "GND_5") (pintype "bidirectional"))
      (node (ref "U8") (pin "8") (pinfunction "GND_8") (pintype "bidirectional"))
      (node (ref "U9") (pin "16") (pinfunction "VSS_16") (pintype "power_in"))
      (node (ref "U9") (pin "32") (pinfunction "VSS_32") (pintype "power_in"))
      (node (ref "U9") (pin "33") (pinfunction "VSS_33") (pintype "power_in"))
      (node (ref "Y2") (pin "1") (pinfunction "GND_1") (pintype "bidirectional"))
      (node (ref "Y2") (pin "2") (pinfunction "GND_2") (pintype "bidirectional"))
    )
    (net (code "93") (name "PPS") (class "Default")
      (node (ref "J1") (pin "19") (pinfunction "19_19") (pintype "bidirectional"))
      (node (ref "P21") (pin "P$1") (pinfunction "P$1_P$1") (pintype "bidirectional"))
      (node (ref "U1") (pin "8") (pinfunction "PPS_8") (pintype "passive"))
      (node (ref "U9") (pin "27") (pinfunction "PB4_27") (pintype "bidirectional"))
    )
    (net (code "94") (name "P_RESET") (class "Default")
      (node (ref "D4") (pin "+") (pinfunction "+_+") (pintype "passive"))
      (node (ref "J1") (pin "22") (pinfunction "22_22") (pintype "bidirectional"))
      (node (ref "P20") (pin "P$1") (pinfunction "P$1_P$1") (pintype "bidirectional"))
      (node (ref "R58") (pin "2") (pinfunction "2_2") (pintype "passive"))
    )
    (net (code "95") (name "RADIO_A_CLK_32M") (class "Default")
      (node (ref "R14") (pin "2") (pinfunction "2_2") (pintype "passive"))
      (node (ref "R42") (pin "1") (pinfunction "1_1") (pintype "passive"))
      (node (ref "U3") (pin "14") (pinfunction "BUSY_14") (pintype "bidirectional"))
    )
    (net (code "96") (name "RADIO_A_CLK_O") (class "Default")
      (node (ref "U1") (pin "48") (pinfunction "RADIO_A_IQ[4]_48") (pintype "passive"))
      (node (ref "U3") (pin "11") (pinfunction "DIO5_11") (pintype "bidirectional"))
    )
    (net (code "97") (name "RADIO_A_CSN") (class "Default")
      (node (ref "U1") (pin "68") (pinfunction "RADIO_A_CSN_68") (pintype "passive"))
      (node (ref "U3") (pin "19") (pinfunction "NSS_19") (pintype "bidirectional"))
    )
    (net (code "98") (name "RADIO_A_IQ0") (class "Default")
      (node (ref "U1") (pin "44") (pinfunction "RADIO_A_IQ[0]_44") (pintype "passive"))
      (node (ref "U3") (pin "13") (pinfunction "DIO1_13") (pintype "bidirectional"))
    )
    (net (code "99") (name "RADIO_A_IQ1") (class "Default")
      (node (ref "U1") (pin "45") (pinfunction "RADIO_A_IQ[1]_45") (pintype "passive"))
      (node (ref "U3") (pin "12") (pinfunction "DIO2_12") (pintype "bidirectional"))
    )
    (net (code "100") (name "RADIO_A_IQ2") (class "Default")
      (node (ref "U1") (pin "49") (pinfunction "RADIO_A_IQ[2]_49") (pintype "passive"))
      (node (ref "U3") (pin "5") (pinfunction "DIO3_5") (pintype "bidirectional"))
    )
    (net (code "101") (name "RADIO_A_IQ3") (class "Default")
      (node (ref "U1") (pin "41") (pinfunction "RADIO_A_IQ[3]_41") (pintype "passive"))
      (node (ref "U3") (pin "21") (pinfunction "DIO4_21") (pintype "bidirectional"))
    )
    (net (code "102") (name "RADIO_A_MISO") (class "Default")
      (node (ref "U1") (pin "42") (pinfunction "RADIO_A_MISO_42") (pintype "passive"))
      (node (ref "U3") (pin "16") (pinfunction "MISO_TX_16") (pintype "bidirectional"))
    )
    (net (code "103") (name "RADIO_A_MOSI") (class "Default")
      (node (ref "U1") (pin "67") (pinfunction "RADIO_A_MOSI_67") (pintype "passive"))
      (node (ref "U3") (pin "17") (pinfunction "MOSI_RX_17") (pintype "bidirectional"))
    )
    (net (code "104") (name "RADIO_A_NRESET") (class "Default")
      (node (ref "U1") (pin "13") (pinfunction "RADIO_CTRL[3]_13") (pintype "passive"))
      (node (ref "U3") (pin "15") (pinfunction "NRESET_15") (pintype "bidirectional"))
    )
    (net (code "105") (name "RADIO_A_SCK") (class "Default")
      (node (ref "U1") (pin "65") (pinfunction "RADIO_A_SCK_65") (pintype "passive"))
      (node (ref "U3") (pin "18") (pinfunction "SCK_18") (pintype "bidirectional"))
    )
    (net (code "106") (name "RADIO_B_CLK_32M") (class "Default")
      (node (ref "R8") (pin "2") (pinfunction "2_2") (pintype "passive"))
      (node (ref "U2") (pin "14") (pinfunction "BUSY_14") (pintype "bidirectional"))
    )
    (net (code "107") (name "RADIO_B_CLK_O") (class "Default")
      (node (ref "U1") (pin "37") (pinfunction "RADIO_B_IQ[4]_37") (pintype "passive"))
      (node (ref "U2") (pin "11") (pinfunction "DIO5_11") (pintype "bidirectional"))
    )
    (net (code "108") (name "RADIO_B_CSN") (class "Default")
      (node (ref "U1") (pin "18") (pinfunction "RADIO_B_CSN_18") (pintype "passive"))
      (node (ref "U2") (pin "19") (pinfunction "NSS_19") (pintype "bidirectional"))
    )
    (net (code "109") (name "RADIO_B_IQ0") (class "Default")
      (node (ref "U1") (pin "35") (pinfunction "RADIO_B_IQ[0]_35") (pintype "passive"))
      (node (ref "U2") (pin "13") (pinfunction "DIO1_13") (pintype "bidirectional"))
    )
    (net (code "110") (name "RADIO_B_IQ1") (class "Default")
      (node (ref "U1") (pin "36") (pinfunction "RADIO_B_IQ[1]_36") (pintype "passive"))
      (node (ref "U2") (pin "12") (pinfunction "DIO2_12") (pintype "bidirectional"))
    )
    (net (code "111") (name "RADIO_B_IQ2") (class "Default")
      (node (ref "U1") (pin "38") (pinfunction "RADIO_B_IQ[2]_38") (pintype "passive"))
      (node (ref "U2") (pin "5") (pinfunction "DIO3_5") (pintype "bidirectional"))
    )
    (net (code "112") (name "RADIO_B_IQ3") (class "Default")
      (node (ref "U1") (pin "32") (pinfunction "RADIO_B_IQ[3]_32") (pintype "passive"))
      (node (ref "U2") (pin "21") (pinfunction "DIO4_21") (pintype "bidirectional"))
    )
    (net (code "113") (name "RADIO_B_MISO") (class "Default")
      (node (ref "U1") (pin "33") (pinfunction "RADIO_B_MISO_33") (pintype "passive"))
      (node (ref "U2") (pin "16") (pinfunction "MISO_TX_16") (pintype "bidirectional"))
    )
    (net (code "114") (name "RADIO_B_MOSI") (class "Default")
      (node (ref "U1") (pin "19") (pinfunction "RADIO_B_MOSI_19") (pintype "passive"))
      (node (ref "U2") (pin "17") (pinfunction "MOSI_RX_17") (pintype "bidirectional"))
    )
    (net (code "115") (name "RADIO_B_NRESET") (class "Default")
      (node (ref "U1") (pin "28") (pinfunction "RADIO_CTRL[9]_28") (pintype "passive"))
      (node (ref "U2") (pin "15") (pinfunction "NRESET_15") (pintype "bidirectional"))
    )
    (net (code "116") (name "RADIO_B_SCK") (class "Default")
      (node (ref "U1") (pin "21") (pinfunction "RADIO_B_SCK_21") (pintype "passive"))
      (node (ref "U2") (pin "18") (pinfunction "SCK_18") (pintype "bidirectional"))
    )
    (net (code "117") (name "RADIO_CTRL1") (class "Default")
      (node (ref "U1") (pin "11") (pinfunction "RADIO_CTRL[1]_11") (pintype "passive"))
    )
    (net (code "118") (name "RXTX_SW") (class "Default")
      (node (ref "C52") (pin "1") (pinfunction "1_1") (pintype "passive"))
      (node (ref "R34") (pin "2") (pinfunction "2_2") (pintype "passive"))
      (node (ref "U6") (pin "6") (pinfunction "CTX_6") (pintype "input"))
    )
    (net (code "119") (name "RX_ON") (class "Default")
      (node (ref "R21") (pin "1") (pinfunction "1_1") (pintype "passive"))
      (node (ref "U1") (pin "59") (pinfunction "GPIO[4]_59") (pintype "passive"))
    )
    (net (code "120") (name "SWCLK") (class "Default")
      (node (ref "P3") (pin "P$1") (pinfunction "P$1_P$1") (pintype "bidirectional"))
      (node (ref "U9") (pin "24") (pinfunction "PA14_24") (pintype "bidirectional"))
    )
    (net (code "121") (name "SWDIO") (class "Default")
      (node (ref "P4") (pin "P$1") (pinfunction "P$1_P$1") (pintype "bidirectional"))
      (node (ref "U9") (pin "23") (pinfunction "PA13_23") (pintype "bidirectional"))
    )
    (net (code "122") (name "SX1261_BUSY") (class "Default")
      (node (ref "J1") (pin "8") (pinfunction "8_8") (pintype "bidirectional"))
      (node (ref "P17") (pin "P$1") (pinfunction "P$1_P$1") (pintype "bidirectional"))
      (node (ref "U8") (pin "14") (pinfunction "BUSY_14") (pintype "bidirectional"))
      (node (ref "U9") (pin "9") (pinfunction "PA3_9") (pintype "bidirectional"))
    )
    (net (code "123") (name "SX1261_DIO1") (class "Default")
      (node (ref "J1") (pin "33") (pinfunction "33_33") (pintype "bidirectional"))
      (node (ref "P15") (pin "P$1") (pinfunction "P$1_P$1") (pintype "bidirectional"))
      (node (ref "U1") (pin "54") (pinfunction "GPIO[7]_54") (pintype "passive"))
      (node (ref "U8") (pin "13") (pinfunction "DIO1_13") (pintype "bidirectional"))
      (node (ref "U9") (pin "15") (pinfunction "PB1_15") (pintype "bidirectional"))
    )
    (net (code "124") (name "SX1261_DIO2") (class "Default")
      (node (ref "J1") (pin "31") (pinfunction "31_31") (pintype "bidirectional"))
      (node (ref "P14") (pin "P$1") (pinfunction "P$1_P$1") (pintype "bidirectional"))
      (node (ref "U8") (pin "12") (pinfunction "DIO2_12") (pintype "bidirectional"))
    )
    (net (code "125") (name "SX1261_NRESET") (class "Default")
      (node (ref "J1") (pin "10") (pinfunction "10_10") (pintype "bidirectional"))
      (node (ref "P18") (pin "P$1") (pinfunction "P$1_P$1") (pintype "bidirectional"))
      (node (ref "R40") (pin "1") (pinfunction "1_1") (pintype "passive"))
      (node (ref "U8") (pin "15") (pinfunction "NRESET_15") (pintype "bidirectional"))
      (node (ref "U9") (pin "18") (pinfunction "PA8_18") (pintype "bidirectional"))
    )
    (net (code "126") (name "SX1261_NSS") (class "Default")
      (node (ref "J1") (pin "25") (pinfunction "25_25") (pintype "bidirectional"))
      (node (ref "P13") (pin "P$1") (pinfunction "P$1_P$1") (pintype "bidirectional"))
      (node (ref "R39") (pin "1") (pinfunction "1_1") (pintype "passive"))
      (node (ref "R41") (pin "1") (pinfunction "1_1") (pintype "passive"))
      (node (ref "U9") (pin "14") (pinfunction "PB0_14") (pintype "bidirectional"))
    )
    (net (code "127") (name "SX1302_CSD") (class "Default")
      (node (ref "R33") (pin "1") (pinfunction "1_1") (pintype "passive"))
      (node (ref "R4") (pin "1") (pinfunction "1_1") (pintype "passive"))
      (node (ref "U1") (pin "10") (pinfunction "RADIO_CTRL[0]_10") (pintype "passive"))
    )
    (net (code "128") (name "SX1302_GPIO8") (class "Default")
      (node (ref "U1") (pin "53") (pinfunction "GPIO[8]_53") (pintype "passive"))
      (node (ref "U9") (pin "26") (pinfunction "PB3_26") (pintype "bidirectional"))
    )
    (net (code "129") (name "SX1302_PA_ON") (class "Default")
      (node (ref "R35") (pin "1") (pinfunction "1_1") (pintype "passive"))
      (node (ref "U1") (pin "16") (pinfunction "RADIO_CTRL[4]_16") (pintype "passive"))
    )
    (net (code "130") (name "SX1302_RESET") (class "Default")
      (node (ref "C63") (pin "2") (pinfunction "2_2") (pintype "passive"))
      (node (ref "D4") (pin "-") (pinfunction "-_-") (pintype "passive"))
      (node (ref "R5") (pin "2") (pinfunction "2_2") (pintype "passive"))
      (node (ref "U1") (pin "7") (pinfunction "RESET_7") (pintype "passive"))
      (node (ref "U9") (pin "8") (pinfunction "PA2_8") (pintype "bidirectional"))
    )
    (net (code "131") (name "SX1302_RXTX_SW") (class "Default")
      (node (ref "R34") (pin "1") (pinfunction "1_1") (pintype "passive"))
      (node (ref "U1") (pin "12") (pinfunction "RADIO_CTRL[2]_12") (pintype "passive"))
    )
    (net (code "132") (name "TCXO_32M_O") (class "Default")
      (node (ref "R24") (pin "2") (pinfunction "2_2") (pintype "passive"))
      (node (ref "R26") (pin "2") (pinfunction "2_2") (pintype "passive"))
      (node (ref "R28") (pin "2") (pinfunction "2_2") (pintype "passive"))
      (node (ref "R37") (pin "2") (pinfunction "2_2") (pintype "passive"))
    )
    (net (code "133") (name "TX_ON") (class "Default")
      (node (ref "R23") (pin "1") (pinfunction "1_1") (pintype "passive"))
      (node (ref "U1") (pin "63") (pinfunction "GPIO[2]_63") (pintype "passive"))
    )
    (net (code "134") (name "USB_D+") (class "Default")
      (node (ref "R9") (pin "2") (pinfunction "2_2") (pintype "passive"))
      (node (ref "U9") (pin "22") (pinfunction "PA12_22") (pintype "bidirectional"))
    )
    (net (code "135") (name "USB_D-") (class "Default")
      (node (ref "R7") (pin "2") (pinfunction "2_2") (pintype "passive"))
      (node (ref "U9") (pin "21") (pinfunction "PA11_21") (pintype "bidirectional"))
    )
    (net (code "136") (name "VCCIO33") (class "Default")
      (node (ref "C10") (pin "2") (pinfunction "2_2") (pintype "passive"))
      (node (ref "C12") (pin "2") (pinfunction "2_2") (pintype "passive"))
      (node (ref "C3") (pin "2") (pinfunction "2_2") (pintype "passive"))
      (node (ref "C4") (pin "2") (pinfunction "2_2") (pintype "passive"))
      (node (ref "C7") (pin "2") (pinfunction "2_2") (pintype "passive"))
      (node (ref "C8") (pin "2") (pinfunction "2_2") (pintype "passive"))
      (node (ref "C83") (pin "2") (pinfunction "2_2") (pintype "passive"))
      (node (ref "C84") (pin "2") (pinfunction "2_2") (pintype "passive"))
      (node (ref "Q1") (pin "3") (pinfunction "D_3") (pintype "passive"))
      (node (ref "R1") (pin "2") (pinfunction "2_2") (pintype "passive"))
      (node (ref "R19") (pin "2") (pinfunction "2_2") (pintype "passive"))
      (node (ref "R20") (pin "2") (pinfunction "2_2") (pintype "passive"))
      (node (ref "R4") (pin "2") (pinfunction "2_2") (pintype "passive"))
      (node (ref "R54") (pin "2") (pinfunction "2_2") (pintype "passive"))
      (node (ref "U1") (pin "14") (pinfunction "VCC_IO_14") (pintype "power_in"))
      (node (ref "U1") (pin "30") (pinfunction "VCC_IO_30") (pintype "power_in"))
      (node (ref "U1") (pin "47") (pinfunction "VCC_IO_47") (pintype "power_in"))
      (node (ref "U1") (pin "61") (pinfunction "VCC_IO_61") (pintype "power_in"))
    )
    (net (code "137") (name "VCC_FEM") (class "Default")
      (node (ref "C35") (pin "2") (pinfunction "2_2") (pintype "passive"))
      (node (ref "C36") (pin "2") (pinfunction "2_2") (pintype "passive"))
      (node (ref "C37") (pin "2") (pinfunction "2_2") (pintype "passive"))
      (node (ref "C38") (pin "2") (pinfunction "2_2") (pintype "passive"))
      (node (ref "C39") (pin "2") (pinfunction "2_2") (pintype "passive"))
      (node (ref "C82") (pin "2") (pinfunction "2_2") (pintype "passive"))
      (node (ref "FB6") (pin "2") (pinfunction "2_2") (pintype "passive"))
      (node (ref "L10") (pin "2") (pinfunction "2_2") (pintype "passive"))
      (node (ref "L11") (pin "2") (pinfunction "2_2") (pintype "passive"))
      (node (ref "U6") (pin "15") (pinfunction "VCC0_15") (pintype "power_in"))
    )
    (net (code "138") (name "VCORE12") (class "Default")
      (node (ref "C1") (pin "2") (pinfunction "2_2") (pintype "passive"))
      (node (ref "C11") (pin "2") (pinfunction "2_2") (pintype "passive"))
      (node (ref "C2") (pin "2") (pinfunction "2_2") (pintype "passive"))
      (node (ref "C5") (pin "2") (pinfunction "2_2") (pintype "passive"))
      (node (ref "C6") (pin "2") (pinfunction "2_2") (pintype "passive"))
      (node (ref "C79") (pin "2") (pinfunction "2_2") (pintype "passive"))
      (node (ref "C9") (pin "2") (pinfunction "2_2") (pintype "passive"))
      (node (ref "FB3") (pin "2") (pinfunction "2_2") (pintype "passive"))
      (node (ref "P23") (pin "P$1") (pinfunction "P$1_P$1") (pintype "bidirectional"))
      (node (ref "R18") (pin "2") (pinfunction "2_2") (pintype "passive"))
      (node (ref "U1") (pin "23") (pinfunction "VCC_CORE_23") (pintype "power_in"))
      (node (ref "U1") (pin "40") (pinfunction "VCC_CORE_40") (pintype "power_in"))
      (node (ref "U1") (pin "5") (pinfunction "VCC_CORE_5") (pintype "power_in"))
      (node (ref "U1") (pin "56") (pinfunction "VCC_CORE_56") (pintype "power_in"))
    )
    (net (code "139") (name "VDD_RADIO") (class "Default")
      (node (ref "C17") (pin "2") (pinfunction "2_2") (pintype "passive"))
      (node (ref "C23") (pin "2") (pinfunction "2_2") (pintype "passive"))
      (node (ref "C57") (pin "2") (pinfunction "2_2") (pintype "passive"))
      (node (ref "C81") (pin "2") (pinfunction "2_2") (pintype "passive"))
      (node (ref "FB1") (pin "1") (pinfunction "1_1") (pintype "passive"))
      (node (ref "FB5") (pin "2") (pinfunction "2_2") (pintype "passive"))
      (node (ref "R25") (pin "2") (pinfunction "2_2") (pintype "passive"))
      (node (ref "R27") (pin "2") (pinfunction "2_2") (pintype "passive"))
      (node (ref "R36") (pin "2") (pinfunction "2_2") (pintype "passive"))
      (node (ref "R39") (pin "2") (pinfunction "2_2") (pintype "passive"))
      (node (ref "R40") (pin "2") (pinfunction "2_2") (pintype "passive"))
      (node (ref "U2") (pin "10") (pinfunction "VBAT_DIO_10") (pintype "bidirectional"))
      (node (ref "U2") (pin "9") (pinfunction "VBAT_RF_9") (pintype "bidirectional"))
      (node (ref "U3") (pin "10") (pinfunction "VBAT_DIO_10") (pintype "bidirectional"))
      (node (ref "U3") (pin "9") (pinfunction "VBAT_RF_9") (pintype "bidirectional"))
      (node (ref "U8") (pin "10") (pinfunction "VBAT_10") (pintype "bidirectional"))
      (node (ref "U8") (pin "11") (pinfunction "VBAT_IO_11") (pintype "bidirectional"))
    )
    (net (code "140") (name "unconnected-(J1-1V5-Pad6)") (class "Default")
      (node (ref "J1") (pin "6") (pinfunction "1V5_6") (pintype "bidirectional"))
    )
    (net (code "141") (name "unconnected-(J1-1V5-Pad28)") (class "Default")
      (node (ref "J1") (pin "28") (pinfunction "1V5_28") (pintype "bidirectional"))
    )
    (net (code "142") (name "unconnected-(J1-1V5-Pad48)") (class "Default")
      (node (ref "J1") (pin "48") (pinfunction "1V5_48") (pintype "bidirectional"))
    )
    (net (code "143") (name "unconnected-(J1-Pad1)") (class "Default")
      (node (ref "J1") (pin "1") (pinfunction "1_1") (pintype "bidirectional"))
    )
    (net (code "144") (name "unconnected-(J1-Pad3)") (class "Default")
      (node (ref "J1") (pin "3") (pinfunction "3_3") (pintype "bidirectional"))
    )
    (net (code "145") (name "unconnected-(J1-Pad5)") (class "Default")
      (node (ref "J1") (pin "5") (pinfunction "5_5") (pintype "bidirectional"))
    )
    (net (code "146") (name "unconnected-(J1-Pad7)") (class "Default")
      (node (ref "J1") (pin "7") (pinfunction "7_7") (pintype "bidirectional"))
    )
    (net (code "147") (name "unconnected-(J1-Pad11)") (class "Default")
      (node (ref "J1") (pin "11") (pinfunction "11_11") (pintype "bidirectional"))
    )
    (net (code "148") (name "unconnected-(J1-Pad12)") (class "Default")
      (node (ref "J1") (pin "12") (pinfunction "12_12") (pintype "bidirectional"))
    )
    (net (code "149") (name "unconnected-(J1-Pad13)") (class "Default")
      (node (ref "J1") (pin "13") (pinfunction "13_13") (pintype "bidirectional"))
    )
    (net (code "150") (name "unconnected-(J1-Pad14)") (class "Default")
      (node (ref "J1") (pin "14") (pinfunction "14_14") (pintype "bidirectional"))
    )
    (net (code "151") (name "unconnected-(J1-Pad16)") (class "Default")
      (node (ref "J1") (pin "16") (pinfunction "16_16") (pintype "bidirectional"))
    )
    (net (code "152") (name "unconnected-(J1-Pad17)") (class "Default")
      (node (ref "J1") (pin "17") (pinfunction "17_17") (pintype "bidirectional"))
    )
    (net (code "153") (name "unconnected-(J1-Pad20)") (class "Default")
      (node (ref "J1") (pin "20") (pinfunction "20_20") (pintype "bidirectional"))
    )
    (net (code "154") (name "unconnected-(J1-Pad23)") (class "Default")
      (node (ref "J1") (pin "23") (pinfunction "23_23") (pintype "bidirectional"))
    )
    (net (code "155") (name "unconnected-(J1-Pad42)") (class "Default")
      (node (ref "J1") (pin "42") (pinfunction "42_42") (pintype "bidirectional"))
    )
    (net (code "156") (name "unconnected-(J1-Pad44)") (class "Default")
      (node (ref "J1") (pin "44") (pinfunction "44_44") (pintype "bidirectional"))
    )
    (net (code "157") (name "unconnected-(J1-Pad46)") (class "Default")
      (node (ref "J1") (pin "46") (pinfunction "46_46") (pintype "bidirectional"))
    )
    (net (code "158") (name "unconnected-(U1-GPIO[1]-Pad64)") (class "Default")
      (node (ref "U1") (pin "64") (pinfunction "GPIO[1]_64") (pintype "passive"))
    )
    (net (code "159") (name "unconnected-(U1-GPIO[3]-Pad60)") (class "Default")
      (node (ref "U1") (pin "60") (pinfunction "GPIO[3]_60") (pintype "passive"))
    )
    (net (code "160") (name "unconnected-(U1-GPIO[5]-Pad58)") (class "Default")
      (node (ref "U1") (pin "58") (pinfunction "GPIO[5]_58") (pintype "passive"))
    )
    (net (code "161") (name "unconnected-(U1-RADIO_CTRL[5]-Pad17)") (class "Default")
      (node (ref "U1") (pin "17") (pinfunction "RADIO_CTRL[5]_17") (pintype "passive"))
    )
    (net (code "162") (name "unconnected-(U1-RADIO_CTRL[6]-Pad22)") (class "Default")
      (node (ref "U1") (pin "22") (pinfunction "RADIO_CTRL[6]_22") (pintype "passive"))
    )
    (net (code "163") (name "unconnected-(U1-RADIO_CTRL[7]-Pad26)") (class "Default")
      (node (ref "U1") (pin "26") (pinfunction "RADIO_CTRL[7]_26") (pintype "passive"))
    )
    (net (code "164") (name "unconnected-(U1-RADIO_CTRL[8]-Pad27)") (class "Default")
      (node (ref "U1") (pin "27") (pinfunction "RADIO_CTRL[8]_27") (pintype "passive"))
    )
    (net (code "165") (name "unconnected-(U1-RADIO_CTRL[10]-Pad29)") (class "Default")
      (node (ref "U1") (pin "29") (pinfunction "RADIO_CTRL[10]_29") (pintype "passive"))
    )
    (net (code "166") (name "unconnected-(U1-RADIO_CTRL[11]-Pad31)") (class "Default")
      (node (ref "U1") (pin "31") (pinfunction "RADIO_CTRL[11]_31") (pintype "passive"))
    )
    (net (code "167") (name "unconnected-(U2-RFO-Pad24)") (class "Default")
      (node (ref "U2") (pin "24") (pinfunction "RFO_24") (pintype "bidirectional"))
    )
    (net (code "168") (name "unconnected-(U2-VR_PA-Pad1)") (class "Default")
      (node (ref "U2") (pin "1") (pinfunction "VR_PA_1") (pintype "bidirectional"))
    )
    (net (code "169") (name "unconnected-(U2-XTB-Pad4)") (class "Default")
      (node (ref "U2") (pin "4") (pinfunction "XTB_4") (pintype "bidirectional"))
    )
    (net (code "170") (name "unconnected-(U3-XTB-Pad4)") (class "Default")
      (node (ref "U3") (pin "4") (pinfunction "XTB_4") (pintype "bidirectional"))
    )
    (net (code "171") (name "unconnected-(U6-N{slash}C-Pad14)") (class "Default")
      (node (ref "U6") (pin "14") (pinfunction "N/C_14") (pintype "passive"))
    )
    (net (code "172") (name "unconnected-(U6-TX_ALT-Pad3)") (class "Default")
      (node (ref "U6") (pin "3") (pinfunction "TX_ALT_3") (pintype "passive"))
    )
    (net (code "173") (name "unconnected-(U8-RFO-Pad23)") (class "Default")
      (node (ref "U8") (pin "23") (pinfunction "RFO_23") (pintype "bidirectional"))
    )
    (net (code "174") (name "unconnected-(U8-VR_PA-Pad24)") (class "Default")
      (node (ref "U8") (pin "24") (pinfunction "VR_PA_24") (pintype "bidirectional"))
    )
    (net (code "175") (name "unconnected-(U8-XTB-Pad4)") (class "Default")
      (node (ref "U8") (pin "4") (pinfunction "XTB_4") (pintype "bidirectional"))
    )
    (net (code "176") (name "unconnected-(U9-PA9-Pad19)") (class "Default")
      (node (ref "U9") (pin "19") (pinfunction "PA9_19") (pintype "bidirectional"))
    )
    (net (code "177") (name "unconnected-(U9-PA10-Pad20)") (class "Default")
      (node (ref "U9") (pin "20") (pinfunction "PA10_20") (pintype "bidirectional"))
    )
    (net (code "178") (name "unconnected-(U9-PA15-Pad25)") (class "Default")
      (node (ref "U9") (pin "25") (pinfunction "PA15_25") (pintype "bidirectional"))
    )
    (net (code "179") (name "unconnected-(U9-PB5-Pad28)") (class "Default")
      (node (ref "U9") (pin "28") (pinfunction "PB5_28") (pintype "bidirectional"))
    )
  )
)
